# backplane_v3.net
KiCad netlist of a schematic drawn in EAGLE
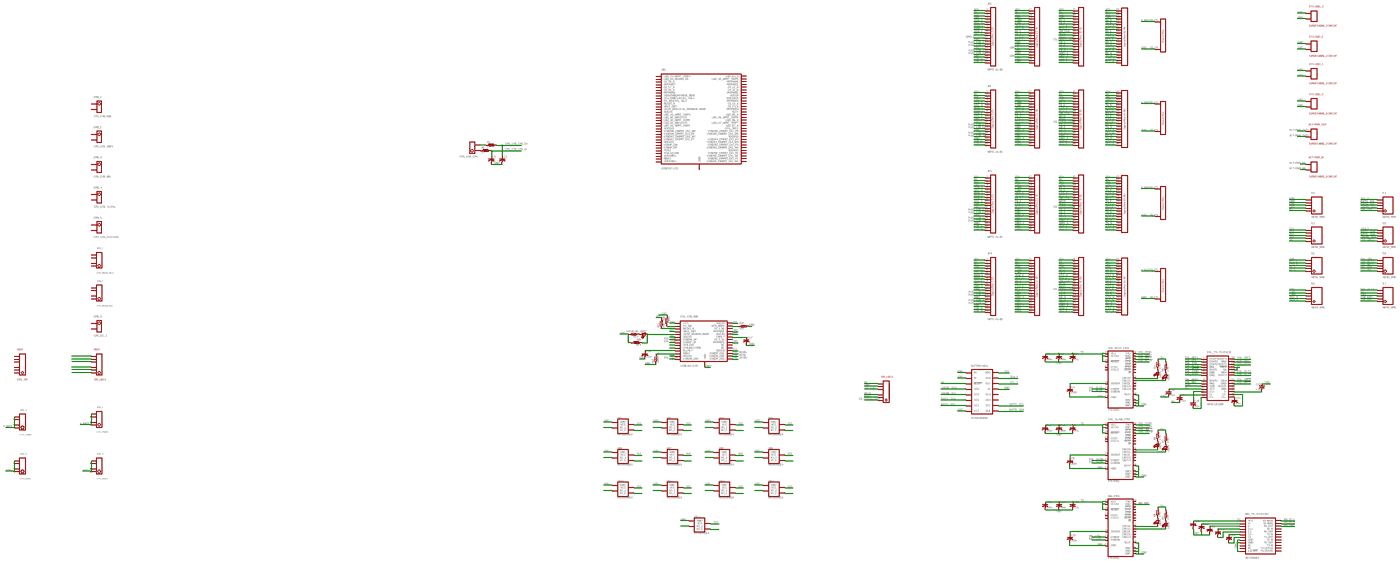
[diagram p0: schematic, sheet 1, overview]
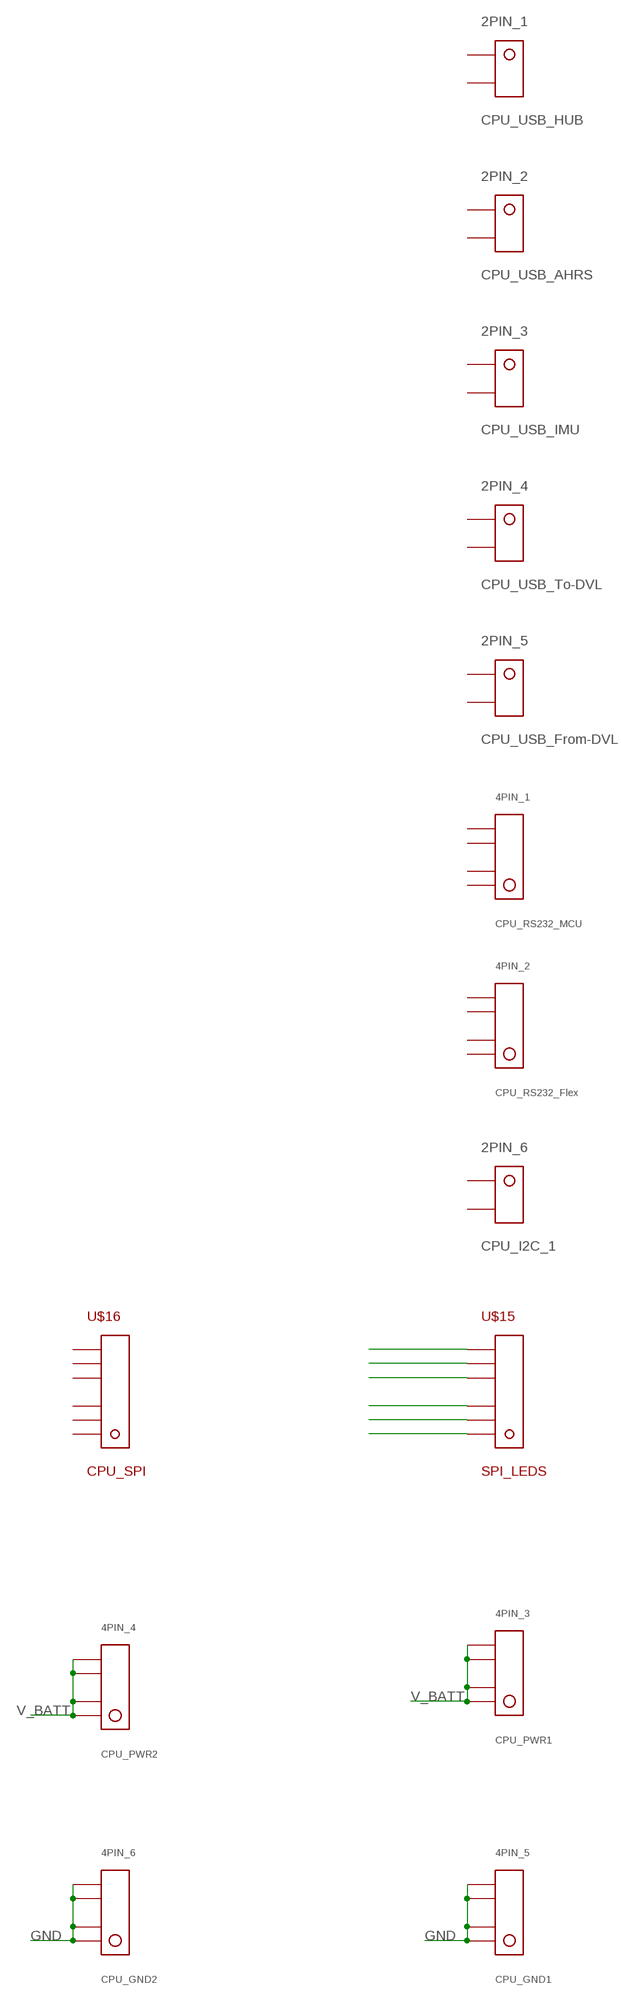
[diagram p1: schematic, sheet 1, part 1 of 4]
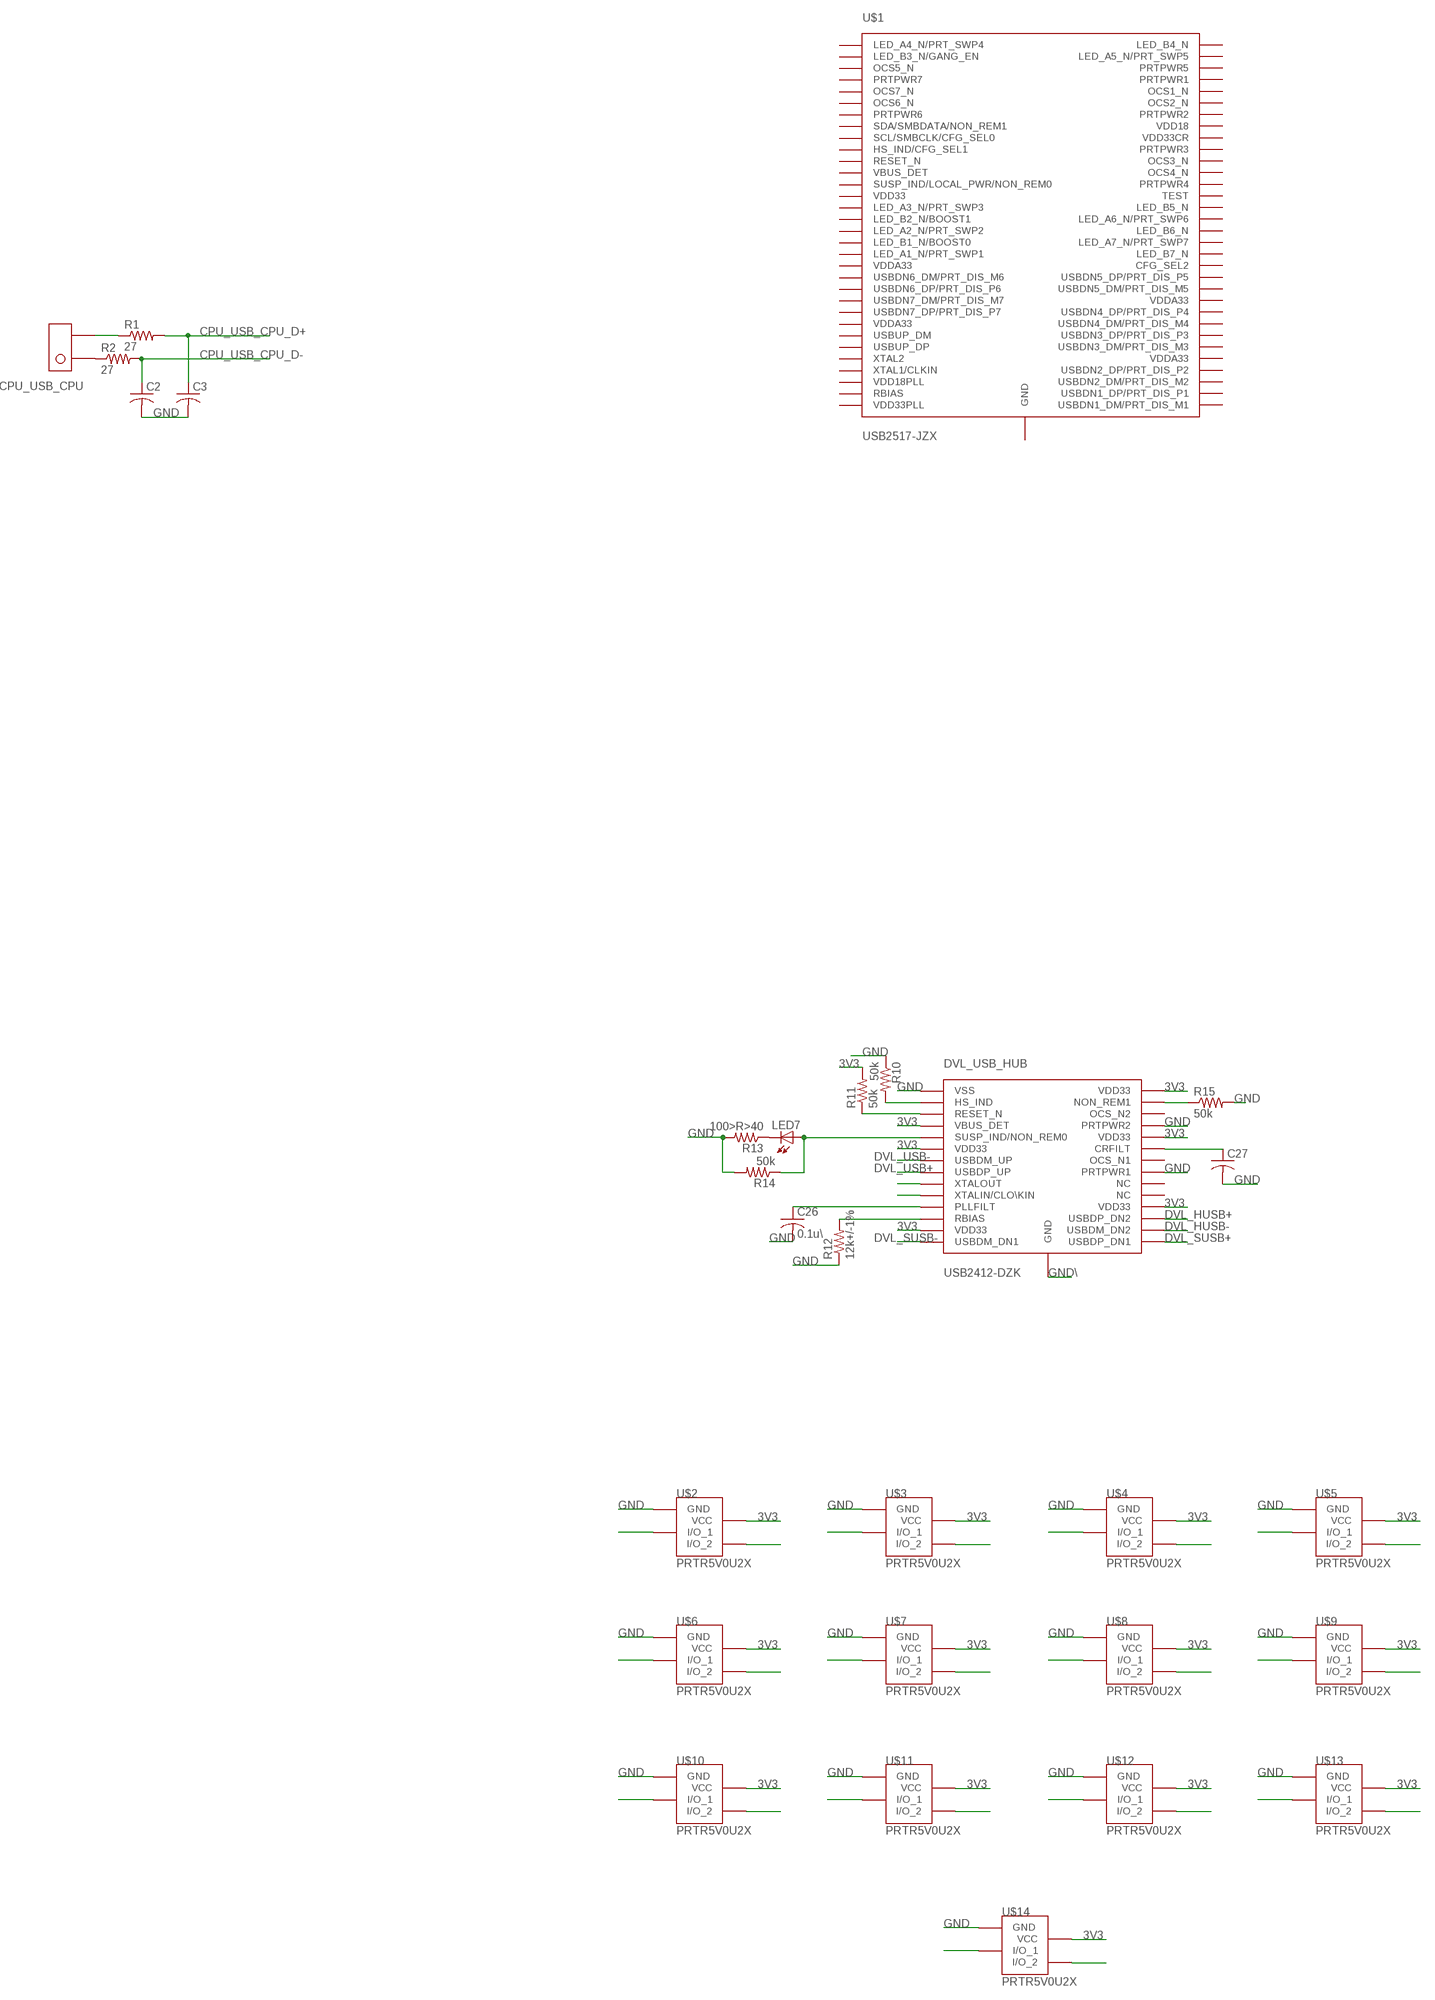
[diagram p2: schematic, sheet 1, part 2 of 4]
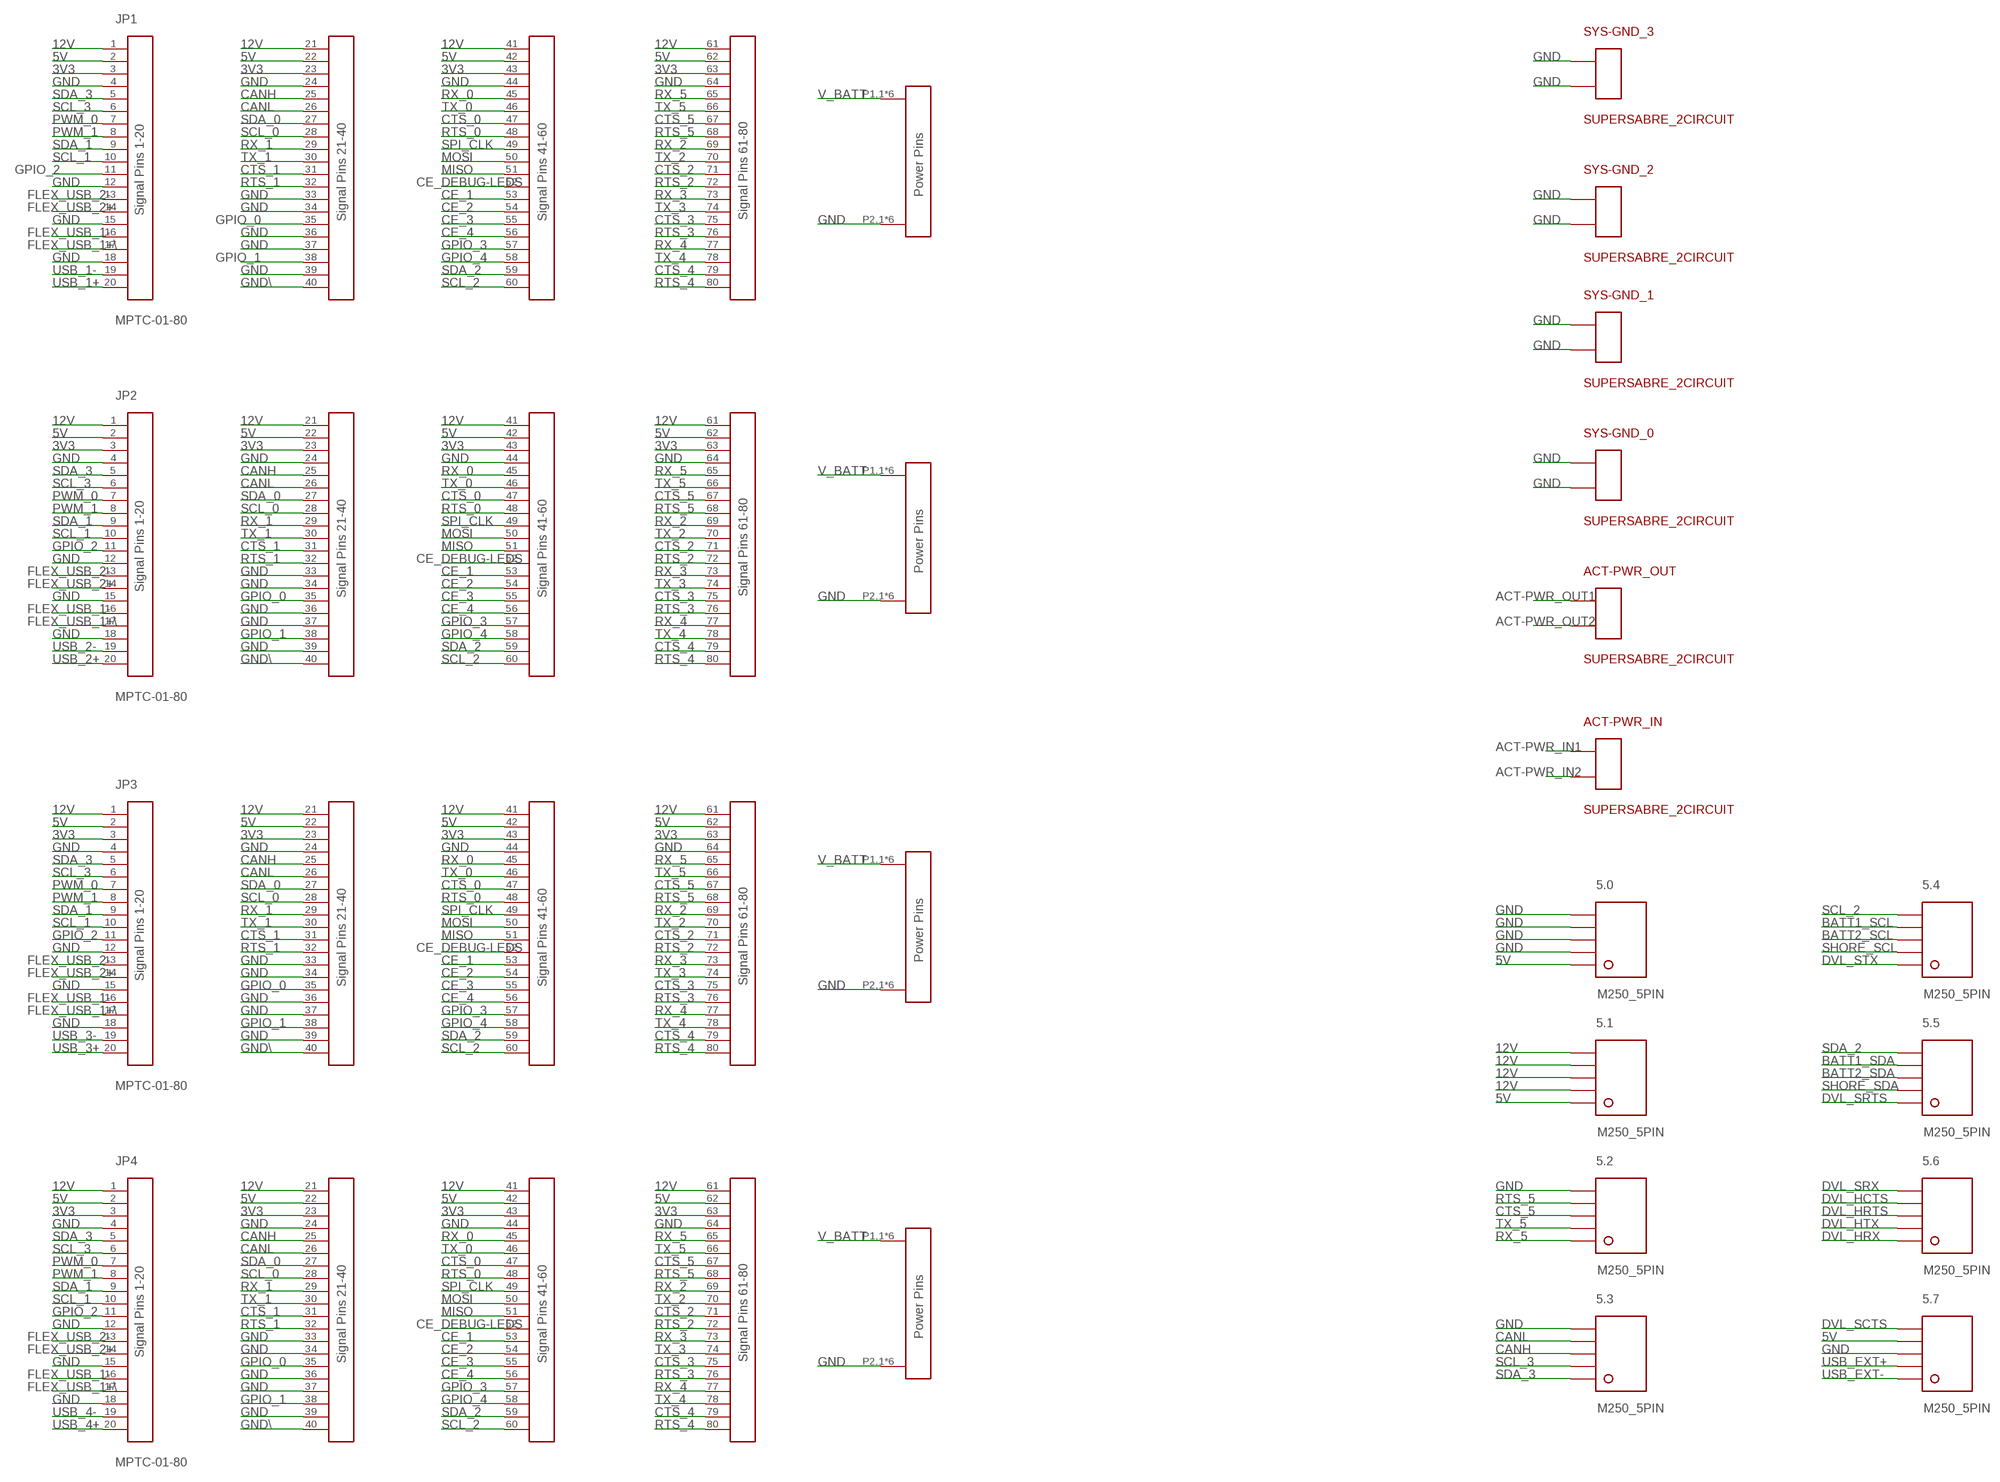
[diagram p3: schematic, sheet 1, part 3 of 4]
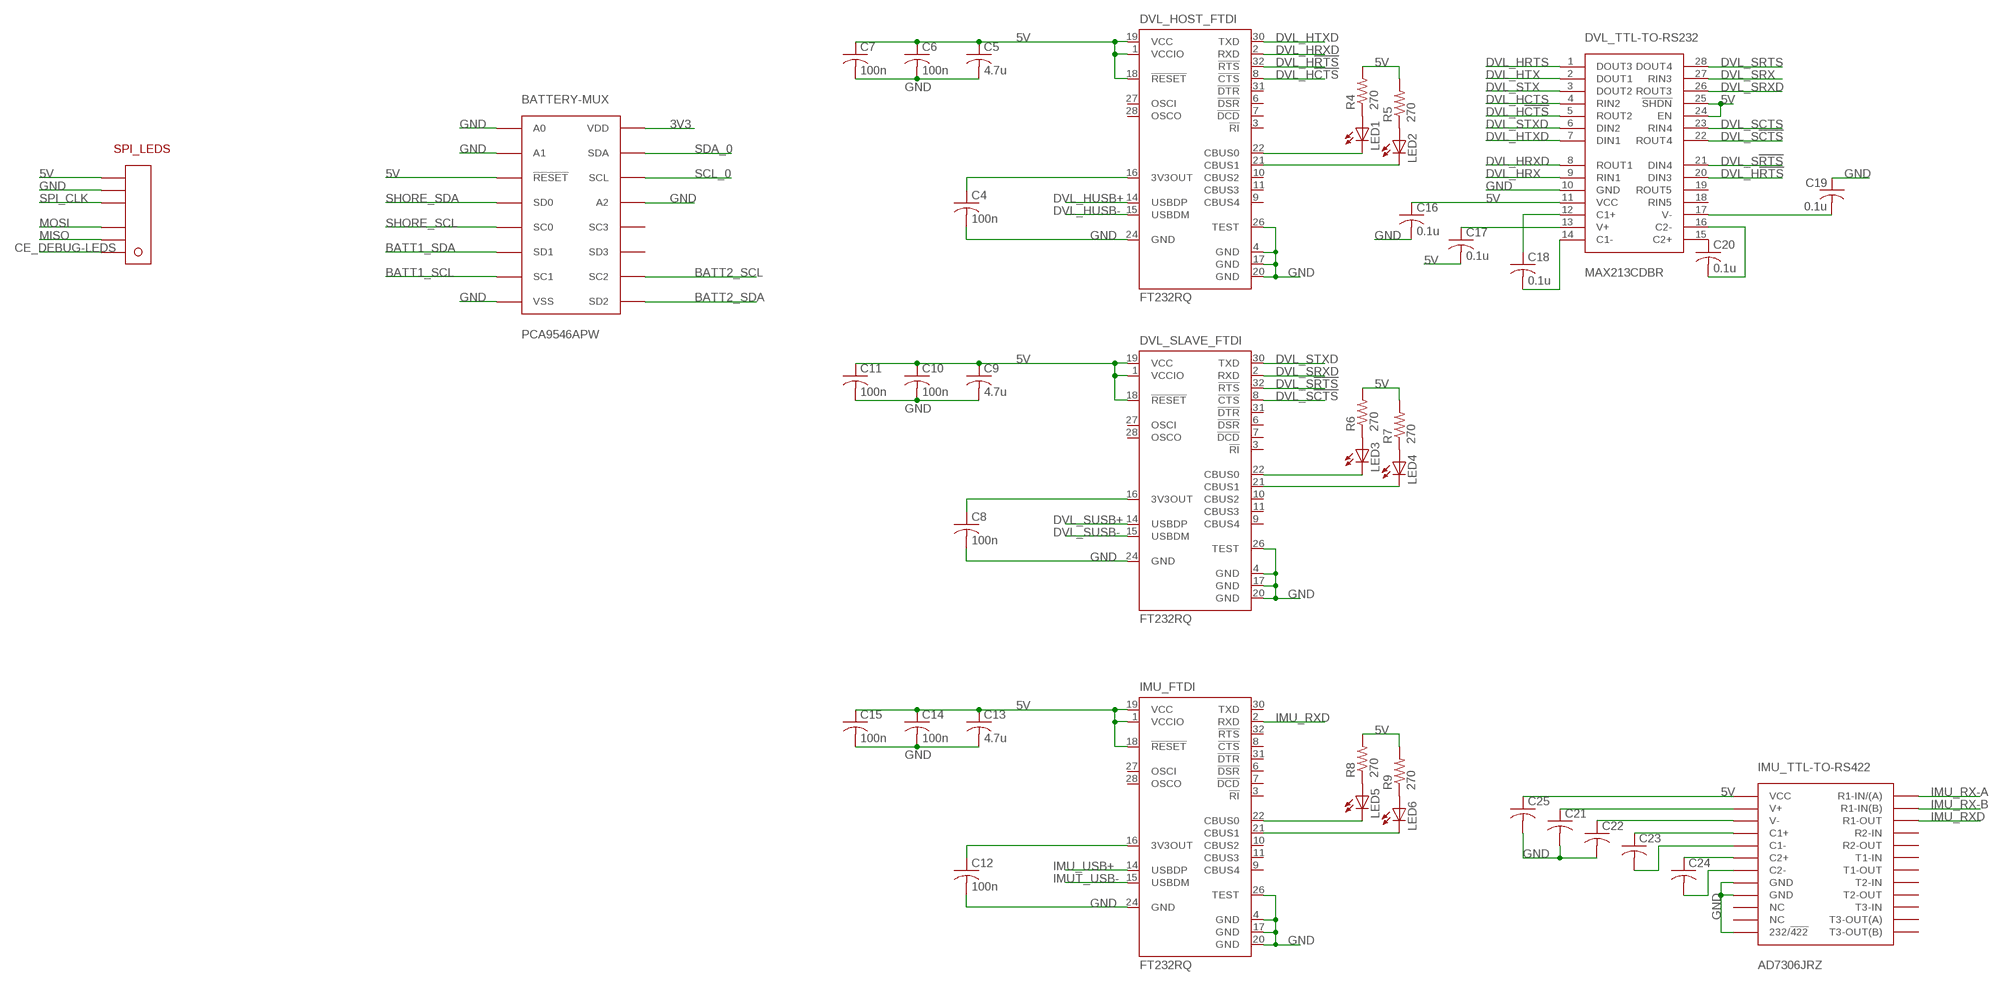
[diagram p4: schematic, sheet 1, part 4 of 4]

(export (version "E")
  (design (tool "Eeschema 10.0.6"))
  (components
    (comp (ref "2PIN_1")
      (value "CPU_USB_HUB")
      (footprint "eagle-import:KK254_VERT_2PIN")
      (libsource (lib "eagle-import") (part "KK254_VERT_2PIN22-29-2021"))
    )
    (comp (ref "2PIN_2")
      (value "CPU_USB_AHRS")
      (footprint "eagle-import:KK254_VERT_2PIN")
      (libsource (lib "eagle-import") (part "KK254_VERT_2PIN22-29-2021"))
    )
    (comp (ref "2PIN_3")
      (value "CPU_USB_IMU")
      (footprint "eagle-import:KK254_VERT_2PIN")
      (libsource (lib "eagle-import") (part "KK254_VERT_2PIN22-29-2021"))
    )
    (comp (ref "2PIN_4")
      (value "CPU_USB_To-DVL")
      (footprint "eagle-import:KK254_VERT_2PIN")
      (libsource (lib "eagle-import") (part "KK254_VERT_2PIN22-29-2021"))
    )
    (comp (ref "2PIN_5")
      (value "CPU_USB_From-DVL")
      (footprint "eagle-import:KK254_VERT_2PIN")
      (libsource (lib "eagle-import") (part "KK254_VERT_2PIN22-29-2021"))
    )
    (comp (ref "2PIN_6")
      (value "CPU_I2C_1")
      (footprint "eagle-import:KK254_VERT_2PIN")
      (libsource (lib "eagle-import") (part "KK254_VERT_2PIN22-29-2021"))
    )
    (comp (ref "4PIN_1")
      (value "CPU_RS232_MCU")
      (footprint "eagle-import:KK254_VERT_4PIN")
      (libsource (lib "eagle-import") (part "KK254_VERT_4PIN22-29-2041"))
    )
    (comp (ref "4PIN_2")
      (value "CPU_RS232_Flex")
      (footprint "eagle-import:KK254_VERT_4PIN")
      (libsource (lib "eagle-import") (part "KK254_VERT_4PIN22-29-2041"))
    )
    (comp (ref "4PIN_3")
      (value "CPU_PWR1")
      (footprint "eagle-import:KK254_VERT_4PIN")
      (libsource (lib "eagle-import") (part "KK254_VERT_4PIN22-29-2041"))
    )
    (comp (ref "4PIN_4")
      (value "CPU_PWR2")
      (footprint "eagle-import:KK254_VERT_4PIN")
      (libsource (lib "eagle-import") (part "KK254_VERT_4PIN22-29-2041"))
    )
    (comp (ref "4PIN_5")
      (value "CPU_GND1")
      (footprint "eagle-import:KK254_VERT_4PIN")
      (libsource (lib "eagle-import") (part "KK254_VERT_4PIN22-29-2041"))
    )
    (comp (ref "4PIN_6")
      (value "CPU_GND2")
      (footprint "eagle-import:KK254_VERT_4PIN")
      (libsource (lib "eagle-import") (part "KK254_VERT_4PIN22-29-2041"))
    )
    (comp (ref "5.0")
      (value "M250_5PIN")
      (footprint "eagle-import:M205_5PIN")
      (libsource (lib "eagle-import") (part "M250_5PIN"))
    )
    (comp (ref "5.1")
      (value "M250_5PIN")
      (footprint "eagle-import:M205_5PIN")
      (libsource (lib "eagle-import") (part "M250_5PIN"))
    )
    (comp (ref "5.2")
      (value "M250_5PIN")
      (footprint "eagle-import:M205_5PIN")
      (libsource (lib "eagle-import") (part "M250_5PIN"))
    )
    (comp (ref "5.3")
      (value "M250_5PIN")
      (footprint "eagle-import:M205_5PIN")
      (libsource (lib "eagle-import") (part "M250_5PIN"))
    )
    (comp (ref "5.4")
      (value "M250_5PIN")
      (footprint "eagle-import:M205_5PIN")
      (libsource (lib "eagle-import") (part "M250_5PIN"))
    )
    (comp (ref "5.5")
      (value "M250_5PIN")
      (footprint "eagle-import:M205_5PIN")
      (libsource (lib "eagle-import") (part "M250_5PIN"))
    )
    (comp (ref "5.6")
      (value "M250_5PIN")
      (footprint "eagle-import:M205_5PIN")
      (libsource (lib "eagle-import") (part "M250_5PIN"))
    )
    (comp (ref "5.7")
      (value "M250_5PIN")
      (footprint "eagle-import:M205_5PIN")
      (libsource (lib "eagle-import") (part "M250_5PIN"))
    )
    (comp (ref "ACT-PWR_IN")
      (value "SUPERSABRE_2CIRCUIT")
      (footprint "eagle-import:SUPERSABRE_2CIRCUIT")
      (libsource (lib "eagle-import") (part "SUPERSABRE_2CIRCUIT"))
    )
    (comp (ref "ACT-PWR_OUT")
      (value "SUPERSABRE_2CIRCUIT")
      (footprint "eagle-import:SUPERSABRE_2CIRCUIT")
      (libsource (lib "eagle-import") (part "SUPERSABRE_2CIRCUIT"))
    )
    (comp (ref "BATTERY-MUX")
      (value "PCA9546APW")
      (footprint "eagle-import:TSSOP16")
      (libsource (lib "eagle-import") (part "PCA9546APW"))
    )
    (comp (ref "C2")
      (value "C-USC0805")
      (footprint "eagle-import:C0805")
      (libsource (lib "eagle-import") (part "C-USC0805"))
    )
    (comp (ref "C3")
      (value "C-USC0805")
      (footprint "eagle-import:C0805")
      (libsource (lib "eagle-import") (part "C-USC0805"))
    )
    (comp (ref "C4")
      (value "100n")
      (footprint "eagle-import:C0805")
      (libsource (lib "eagle-import") (part "C-USC0805"))
    )
    (comp (ref "C5")
      (value "4.7u")
      (footprint "eagle-import:C0805")
      (libsource (lib "eagle-import") (part "C-USC0805"))
    )
    (comp (ref "C6")
      (value "100n")
      (footprint "eagle-import:C0805")
      (libsource (lib "eagle-import") (part "C-USC0805"))
    )
    (comp (ref "C7")
      (value "100n")
      (footprint "eagle-import:C0805")
      (libsource (lib "eagle-import") (part "C-USC0805"))
    )
    (comp (ref "C8")
      (value "100n")
      (footprint "eagle-import:C0805")
      (libsource (lib "eagle-import") (part "C-USC0805"))
    )
    (comp (ref "C9")
      (value "4.7u")
      (footprint "eagle-import:C0805")
      (libsource (lib "eagle-import") (part "C-USC0805"))
    )
    (comp (ref "C10")
      (value "100n")
      (footprint "eagle-import:C0805")
      (libsource (lib "eagle-import") (part "C-USC0805"))
    )
    (comp (ref "C11")
      (value "100n")
      (footprint "eagle-import:C0805")
      (libsource (lib "eagle-import") (part "C-USC0805"))
    )
    (comp (ref "C12")
      (value "100n")
      (footprint "eagle-import:C0805")
      (libsource (lib "eagle-import") (part "C-USC0805"))
    )
    (comp (ref "C13")
      (value "4.7u")
      (footprint "eagle-import:C0805")
      (libsource (lib "eagle-import") (part "C-USC0805"))
    )
    (comp (ref "C14")
      (value "100n")
      (footprint "eagle-import:C0805")
      (libsource (lib "eagle-import") (part "C-USC0805"))
    )
    (comp (ref "C15")
      (value "100n")
      (footprint "eagle-import:C0805")
      (libsource (lib "eagle-import") (part "C-USC0805"))
    )
    (comp (ref "C16")
      (value "0.1u")
      (footprint "eagle-import:C0805")
      (libsource (lib "eagle-import") (part "C-USC0805"))
    )
    (comp (ref "C17")
      (value "0.1u")
      (footprint "eagle-import:C0805")
      (libsource (lib "eagle-import") (part "C-USC0805"))
    )
    (comp (ref "C18")
      (value "0.1u")
      (footprint "eagle-import:C0805")
      (libsource (lib "eagle-import") (part "C-USC0805"))
    )
    (comp (ref "C19")
      (value "0.1u")
      (footprint "eagle-import:C0805")
      (libsource (lib "eagle-import") (part "C-USC0805"))
    )
    (comp (ref "C20")
      (value "0.1u")
      (footprint "eagle-import:C0805")
      (libsource (lib "eagle-import") (part "C-USC0805"))
    )
    (comp (ref "C21")
      (value "C-USC0805")
      (footprint "eagle-import:C0805")
      (libsource (lib "eagle-import") (part "C-USC0805"))
    )
    (comp (ref "C22")
      (value "C-USC0805")
      (footprint "eagle-import:C0805")
      (libsource (lib "eagle-import") (part "C-USC0805"))
    )
    (comp (ref "C23")
      (value "C-USC0805")
      (footprint "eagle-import:C0805")
      (libsource (lib "eagle-import") (part "C-USC0805"))
    )
    (comp (ref "C24")
      (value "C-USC0805")
      (footprint "eagle-import:C0805")
      (libsource (lib "eagle-import") (part "C-USC0805"))
    )
    (comp (ref "C25")
      (value "C-USC0805")
      (footprint "eagle-import:C0805")
      (libsource (lib "eagle-import") (part "C-USC0805"))
    )
    (comp (ref "C26")
      (value "0.1u\\")
      (footprint "eagle-import:C0805")
      (libsource (lib "eagle-import") (part "C-USC0805"))
    )
    (comp (ref "C27")
      (value "C-USC0805")
      (footprint "eagle-import:C0805")
      (libsource (lib "eagle-import") (part "C-USC0805"))
    )
    (comp (ref "CPU_USB_CPU")
      (value "KK254_VERT_2PIN22-29-2021")
      (footprint "eagle-import:KK254_VERT_2PIN")
      (libsource (lib "eagle-import") (part "KK254_VERT_2PIN22-29-2021"))
    )
    (comp (ref "DVL_HOST_FTDI")
      (value "FT232RQ")
      (footprint "eagle-import:QFN32")
      (libsource (lib "eagle-import") (part "FT232RQ"))
    )
    (comp (ref "DVL_SLAVE_FTDI")
      (value "FT232RQ")
      (footprint "eagle-import:QFN32")
      (libsource (lib "eagle-import") (part "FT232RQ"))
    )
    (comp (ref "DVL_TTL-TO-RS232")
      (value "MAX213CDBR")
      (footprint "eagle-import:SSOP28DB")
      (libsource (lib "eagle-import") (part "MAX213CDBR"))
    )
    (comp (ref "DVL_USB_HUB")
      (value "USB2412-DZK")
      (footprint "eagle-import:QFN-28")
      (libsource (lib "eagle-import") (part "USB2412-DZK"))
    )
    (comp (ref "IMU_FTDI")
      (value "FT232RQ")
      (footprint "eagle-import:QFN32")
      (libsource (lib "eagle-import") (part "FT232RQ"))
    )
    (comp (ref "IMU_TTL-TO-RS422")
      (value "AD7306JRZ")
      (footprint "eagle-import:SOIC-24")
      (libsource (lib "eagle-import") (part "AD7306JRZ"))
    )
    (comp (ref "JP1")
      (value "MPTC-01-80")
      (footprint "eagle-import:MPTC-01-80")
      (libsource (lib "eagle-import") (part "MPTC-01-80"))
    )
    (comp (ref "JP2")
      (value "MPTC-01-80")
      (footprint "eagle-import:MPTC-01-80")
      (libsource (lib "eagle-import") (part "MPTC-01-80"))
    )
    (comp (ref "JP3")
      (value "MPTC-01-80")
      (footprint "eagle-import:MPTC-01-80")
      (libsource (lib "eagle-import") (part "MPTC-01-80"))
    )
    (comp (ref "JP4")
      (value "MPTC-01-80")
      (footprint "eagle-import:MPTC-01-80")
      (libsource (lib "eagle-import") (part "MPTC-01-80"))
    )
    (comp (ref "LED1")
      (value "LEDCHIPLED_0805")
      (footprint "eagle-import:CHIPLED_0805")
      (libsource (lib "eagle-import") (part "LEDCHIPLED_0805"))
    )
    (comp (ref "LED2")
      (value "LEDCHIPLED_0805")
      (footprint "eagle-import:CHIPLED_0805")
      (libsource (lib "eagle-import") (part "LEDCHIPLED_0805"))
    )
    (comp (ref "LED3")
      (value "LEDCHIPLED_0805")
      (footprint "eagle-import:CHIPLED_0805")
      (libsource (lib "eagle-import") (part "LEDCHIPLED_0805"))
    )
    (comp (ref "LED4")
      (value "LEDCHIPLED_0805")
      (footprint "eagle-import:CHIPLED_0805")
      (libsource (lib "eagle-import") (part "LEDCHIPLED_0805"))
    )
    (comp (ref "LED5")
      (value "LEDCHIPLED_0805")
      (footprint "eagle-import:CHIPLED_0805")
      (libsource (lib "eagle-import") (part "LEDCHIPLED_0805"))
    )
    (comp (ref "LED6")
      (value "LEDCHIPLED_0805")
      (footprint "eagle-import:CHIPLED_0805")
      (libsource (lib "eagle-import") (part "LEDCHIPLED_0805"))
    )
    (comp (ref "LED7")
      (value "LEDCHIPLED_0805")
      (footprint "eagle-import:CHIPLED_0805")
      (libsource (lib "eagle-import") (part "LEDCHIPLED_0805"))
    )
    (comp (ref "R1")
      (value "27")
      (footprint "eagle-import:R0805")
      (libsource (lib "eagle-import") (part "R-US_R0805"))
    )
    (comp (ref "R2")
      (value "27")
      (footprint "eagle-import:R0805")
      (libsource (lib "eagle-import") (part "R-US_R0805"))
    )
    (comp (ref "R4")
      (value "270")
      (footprint "eagle-import:R0805")
      (libsource (lib "eagle-import") (part "R-US_R0805"))
    )
    (comp (ref "R5")
      (value "270")
      (footprint "eagle-import:R0805")
      (libsource (lib "eagle-import") (part "R-US_R0805"))
    )
    (comp (ref "R6")
      (value "270")
      (footprint "eagle-import:R0805")
      (libsource (lib "eagle-import") (part "R-US_R0805"))
    )
    (comp (ref "R7")
      (value "270")
      (footprint "eagle-import:R0805")
      (libsource (lib "eagle-import") (part "R-US_R0805"))
    )
    (comp (ref "R8")
      (value "270")
      (footprint "eagle-import:R0805")
      (libsource (lib "eagle-import") (part "R-US_R0805"))
    )
    (comp (ref "R9")
      (value "270")
      (footprint "eagle-import:R0805")
      (libsource (lib "eagle-import") (part "R-US_R0805"))
    )
    (comp (ref "R10")
      (value "50k")
      (footprint "eagle-import:R0805")
      (libsource (lib "eagle-import") (part "R-US_R0805"))
    )
    (comp (ref "R11")
      (value "50k")
      (footprint "eagle-import:R0805")
      (libsource (lib "eagle-import") (part "R-US_R0805"))
    )
    (comp (ref "R12")
      (value "12k+/-1%")
      (footprint "eagle-import:R0805")
      (libsource (lib "eagle-import") (part "R-US_R0805"))
    )
    (comp (ref "R13")
      (value "100>R>40")
      (footprint "eagle-import:R0805")
      (libsource (lib "eagle-import") (part "R-US_R0805"))
    )
    (comp (ref "R14")
      (value "50k")
      (footprint "eagle-import:R0805")
      (libsource (lib "eagle-import") (part "R-US_R0805"))
    )
    (comp (ref "R15")
      (value "50k")
      (footprint "eagle-import:R0805")
      (libsource (lib "eagle-import") (part "R-US_R0805"))
    )
    (comp (ref "SPI_LEDS")
      (value "KK254_6PIN")
      (footprint "eagle-import:KK254_6PIN")
      (libsource (lib "eagle-import") (part "KK254_6PIN"))
    )
    (comp (ref "SYS-GND_0")
      (value "SUPERSABRE_2CIRCUIT")
      (footprint "eagle-import:SUPERSABRE_2CIRCUIT")
      (libsource (lib "eagle-import") (part "SUPERSABRE_2CIRCUIT"))
    )
    (comp (ref "SYS-GND_1")
      (value "SUPERSABRE_2CIRCUIT")
      (footprint "eagle-import:SUPERSABRE_2CIRCUIT")
      (libsource (lib "eagle-import") (part "SUPERSABRE_2CIRCUIT"))
    )
    (comp (ref "SYS-GND_2")
      (value "SUPERSABRE_2CIRCUIT")
      (footprint "eagle-import:SUPERSABRE_2CIRCUIT")
      (libsource (lib "eagle-import") (part "SUPERSABRE_2CIRCUIT"))
    )
    (comp (ref "SYS-GND_3")
      (value "SUPERSABRE_2CIRCUIT")
      (footprint "eagle-import:SUPERSABRE_2CIRCUIT")
      (libsource (lib "eagle-import") (part "SUPERSABRE_2CIRCUIT"))
    )
    (comp (ref "U$1")
      (value "USB2517-JZX")
      (footprint "eagle-import:QFN-64")
      (libsource (lib "eagle-import") (part "USB2517-JZX"))
    )
    (comp (ref "U$2")
      (value "PRTR5V0U2X")
      (footprint "eagle-import:SOT143B")
      (libsource (lib "eagle-import") (part "PRTR5V0U2X"))
    )
    (comp (ref "U$3")
      (value "PRTR5V0U2X")
      (footprint "eagle-import:SOT143B")
      (libsource (lib "eagle-import") (part "PRTR5V0U2X"))
    )
    (comp (ref "U$4")
      (value "PRTR5V0U2X")
      (footprint "eagle-import:SOT143B")
      (libsource (lib "eagle-import") (part "PRTR5V0U2X"))
    )
    (comp (ref "U$5")
      (value "PRTR5V0U2X")
      (footprint "eagle-import:SOT143B")
      (libsource (lib "eagle-import") (part "PRTR5V0U2X"))
    )
    (comp (ref "U$6")
      (value "PRTR5V0U2X")
      (footprint "eagle-import:SOT143B")
      (libsource (lib "eagle-import") (part "PRTR5V0U2X"))
    )
    (comp (ref "U$7")
      (value "PRTR5V0U2X")
      (footprint "eagle-import:SOT143B")
      (libsource (lib "eagle-import") (part "PRTR5V0U2X"))
    )
    (comp (ref "U$8")
      (value "PRTR5V0U2X")
      (footprint "eagle-import:SOT143B")
      (libsource (lib "eagle-import") (part "PRTR5V0U2X"))
    )
    (comp (ref "U$9")
      (value "PRTR5V0U2X")
      (footprint "eagle-import:SOT143B")
      (libsource (lib "eagle-import") (part "PRTR5V0U2X"))
    )
    (comp (ref "U$10")
      (value "PRTR5V0U2X")
      (footprint "eagle-import:SOT143B")
      (libsource (lib "eagle-import") (part "PRTR5V0U2X"))
    )
    (comp (ref "U$11")
      (value "PRTR5V0U2X")
      (footprint "eagle-import:SOT143B")
      (libsource (lib "eagle-import") (part "PRTR5V0U2X"))
    )
    (comp (ref "U$12")
      (value "PRTR5V0U2X")
      (footprint "eagle-import:SOT143B")
      (libsource (lib "eagle-import") (part "PRTR5V0U2X"))
    )
    (comp (ref "U$13")
      (value "PRTR5V0U2X")
      (footprint "eagle-import:SOT143B")
      (libsource (lib "eagle-import") (part "PRTR5V0U2X"))
    )
    (comp (ref "U$14")
      (value "PRTR5V0U2X")
      (footprint "eagle-import:SOT143B")
      (libsource (lib "eagle-import") (part "PRTR5V0U2X"))
    )
    (comp (ref "U$15")
      (value "SPI_LEDS")
      (footprint "eagle-import:KK254_6PIN")
      (libsource (lib "eagle-import") (part "KK254_6PIN"))
    )
    (comp (ref "U$16")
      (value "CPU_SPI")
      (footprint "eagle-import:KK254_6PIN")
      (libsource (lib "eagle-import") (part "KK254_6PIN"))
    )
  )
  (nets
    (net (code "1") (name "/3V3") (class "Default")
      (node (ref "BATTERY-MUX") (pin "P$16") (pinfunction "VDD_P$16") (pintype "bidirectional"))
      (node (ref "DVL_USB_HUB") (pin "P$10") (pinfunction "VDD33_P$10") (pintype "bidirectional"))
      (node (ref "DVL_USB_HUB") (pin "P$14") (pinfunction "VDD33_P$14") (pintype "bidirectional"))
      (node (ref "DVL_USB_HUB") (pin "P$18") (pinfunction "VBUS_DET_P$18") (pintype "bidirectional"))
      (node (ref "DVL_USB_HUB") (pin "P$20") (pinfunction "VDD33_P$20") (pintype "bidirectional"))
      (node (ref "DVL_USB_HUB") (pin "P$27") (pinfunction "VDD33_P$27") (pintype "bidirectional"))
      (node (ref "DVL_USB_HUB") (pin "P$4") (pinfunction "VDD33_P$4") (pintype "bidirectional"))
      (node (ref "JP1") (pin "23") (pinfunction "P$23_23") (pintype "bidirectional"))
      (node (ref "JP1") (pin "3") (pinfunction "P$3_3") (pintype "bidirectional"))
      (node (ref "JP1") (pin "43") (pinfunction "P$43_43") (pintype "bidirectional"))
      (node (ref "JP1") (pin "63") (pinfunction "P$63_63") (pintype "bidirectional"))
      (node (ref "JP2") (pin "23") (pinfunction "P$23_23") (pintype "bidirectional"))
      (node (ref "JP2") (pin "3") (pinfunction "P$3_3") (pintype "bidirectional"))
      (node (ref "JP2") (pin "43") (pinfunction "P$43_43") (pintype "bidirectional"))
      (node (ref "JP2") (pin "63") (pinfunction "P$63_63") (pintype "bidirectional"))
      (node (ref "JP3") (pin "23") (pinfunction "P$23_23") (pintype "bidirectional"))
      (node (ref "JP3") (pin "3") (pinfunction "P$3_3") (pintype "bidirectional"))
      (node (ref "JP3") (pin "43") (pinfunction "P$43_43") (pintype "bidirectional"))
      (node (ref "JP3") (pin "63") (pinfunction "P$63_63") (pintype "bidirectional"))
      (node (ref "JP4") (pin "23") (pinfunction "P$23_23") (pintype "bidirectional"))
      (node (ref "JP4") (pin "3") (pinfunction "P$3_3") (pintype "bidirectional"))
      (node (ref "JP4") (pin "43") (pinfunction "P$43_43") (pintype "bidirectional"))
      (node (ref "JP4") (pin "63") (pinfunction "P$63_63") (pintype "bidirectional"))
      (node (ref "R11") (pin "2") (pinfunction "2_2") (pintype "passive"))
      (node (ref "U$10") (pin "P$4") (pinfunction "VCC_P$4") (pintype "bidirectional"))
      (node (ref "U$11") (pin "P$4") (pinfunction "VCC_P$4") (pintype "bidirectional"))
      (node (ref "U$12") (pin "P$4") (pinfunction "VCC_P$4") (pintype "bidirectional"))
      (node (ref "U$13") (pin "P$4") (pinfunction "VCC_P$4") (pintype "bidirectional"))
      (node (ref "U$14") (pin "P$4") (pinfunction "VCC_P$4") (pintype "bidirectional"))
      (node (ref "U$2") (pin "P$4") (pinfunction "VCC_P$4") (pintype "bidirectional"))
      (node (ref "U$3") (pin "P$4") (pinfunction "VCC_P$4") (pintype "bidirectional"))
      (node (ref "U$4") (pin "P$4") (pinfunction "VCC_P$4") (pintype "bidirectional"))
      (node (ref "U$5") (pin "P$4") (pinfunction "VCC_P$4") (pintype "bidirectional"))
      (node (ref "U$6") (pin "P$4") (pinfunction "VCC_P$4") (pintype "bidirectional"))
      (node (ref "U$7") (pin "P$4") (pinfunction "VCC_P$4") (pintype "bidirectional"))
      (node (ref "U$8") (pin "P$4") (pinfunction "VCC_P$4") (pintype "bidirectional"))
      (node (ref "U$9") (pin "P$4") (pinfunction "VCC_P$4") (pintype "bidirectional"))
    )
    (net (code "2") (name "/5V") (class "Default")
      (node (ref "5.0") (pin "P$1") (pinfunction "P$1_P$1") (pintype "bidirectional"))
      (node (ref "5.0") (pin "P$2") (pinfunction "P$1_P$2") (pintype "bidirectional"))
      (node (ref "5.1") (pin "P$1") (pinfunction "P$1_P$1") (pintype "bidirectional"))
      (node (ref "5.1") (pin "P$2") (pinfunction "P$1_P$2") (pintype "bidirectional"))
      (node (ref "5.7") (pin "P$7") (pinfunction "P$4_P$7") (pintype "bidirectional"))
      (node (ref "5.7") (pin "P$8") (pinfunction "P$4_P$8") (pintype "bidirectional"))
      (node (ref "BATTERY-MUX") (pin "P$3") (pinfunction "~{RESET}_P$3") (pintype "bidirectional"))
      (node (ref "C10") (pin "1") (pinfunction "1_1") (pintype "passive"))
      (node (ref "C11") (pin "1") (pinfunction "1_1") (pintype "passive"))
      (node (ref "C13") (pin "1") (pinfunction "1_1") (pintype "passive"))
      (node (ref "C14") (pin "1") (pinfunction "1_1") (pintype "passive"))
      (node (ref "C15") (pin "1") (pinfunction "1_1") (pintype "passive"))
      (node (ref "C16") (pin "1") (pinfunction "1_1") (pintype "passive"))
      (node (ref "C17") (pin "2") (pinfunction "2_2") (pintype "passive"))
      (node (ref "C25") (pin "1") (pinfunction "1_1") (pintype "passive"))
      (node (ref "C5") (pin "1") (pinfunction "1_1") (pintype "passive"))
      (node (ref "C6") (pin "1") (pinfunction "1_1") (pintype "passive"))
      (node (ref "C7") (pin "1") (pinfunction "1_1") (pintype "passive"))
      (node (ref "C9") (pin "1") (pinfunction "1_1") (pintype "passive"))
      (node (ref "DVL_HOST_FTDI") (pin "1") (pinfunction "VCCIO_1") (pintype "power_in"))
      (node (ref "DVL_HOST_FTDI") (pin "18") (pinfunction "~{RESET}_18") (pintype "input"))
      (node (ref "DVL_HOST_FTDI") (pin "19") (pinfunction "VCC_19") (pintype "power_in"))
      (node (ref "DVL_SLAVE_FTDI") (pin "1") (pinfunction "VCCIO_1") (pintype "power_in"))
      (node (ref "DVL_SLAVE_FTDI") (pin "18") (pinfunction "~{RESET}_18") (pintype "input"))
      (node (ref "DVL_SLAVE_FTDI") (pin "19") (pinfunction "VCC_19") (pintype "power_in"))
      (node (ref "DVL_TTL-TO-RS232") (pin "11") (pinfunction "VCC_11") (pintype "bidirectional"))
      (node (ref "DVL_TTL-TO-RS232") (pin "24") (pinfunction "EN_24") (pintype "bidirectional"))
      (node (ref "DVL_TTL-TO-RS232") (pin "25") (pinfunction "~{SHDN}_25") (pintype "bidirectional"))
      (node (ref "IMU_FTDI") (pin "1") (pinfunction "VCCIO_1") (pintype "power_in"))
      (node (ref "IMU_FTDI") (pin "18") (pinfunction "~{RESET}_18") (pintype "input"))
      (node (ref "IMU_FTDI") (pin "19") (pinfunction "VCC_19") (pintype "power_in"))
      (node (ref "IMU_TTL-TO-RS422") (pin "P$7") (pinfunction "VCC_P$7") (pintype "bidirectional"))
      (node (ref "JP1") (pin "2") (pinfunction "P$2_2") (pintype "bidirectional"))
      (node (ref "JP1") (pin "22") (pinfunction "P$22_22") (pintype "bidirectional"))
      (node (ref "JP1") (pin "42") (pinfunction "P$42_42") (pintype "bidirectional"))
      (node (ref "JP1") (pin "62") (pinfunction "P$62_62") (pintype "bidirectional"))
      (node (ref "JP2") (pin "2") (pinfunction "P$2_2") (pintype "bidirectional"))
      (node (ref "JP2") (pin "22") (pinfunction "P$22_22") (pintype "bidirectional"))
      (node (ref "JP2") (pin "42") (pinfunction "P$42_42") (pintype "bidirectional"))
      (node (ref "JP2") (pin "62") (pinfunction "P$62_62") (pintype "bidirectional"))
      (node (ref "JP3") (pin "2") (pinfunction "P$2_2") (pintype "bidirectional"))
      (node (ref "JP3") (pin "22") (pinfunction "P$22_22") (pintype "bidirectional"))
      (node (ref "JP3") (pin "42") (pinfunction "P$42_42") (pintype "bidirectional"))
      (node (ref "JP3") (pin "62") (pinfunction "P$62_62") (pintype "bidirectional"))
      (node (ref "JP4") (pin "2") (pinfunction "P$2_2") (pintype "bidirectional"))
      (node (ref "JP4") (pin "22") (pinfunction "P$22_22") (pintype "bidirectional"))
      (node (ref "JP4") (pin "42") (pinfunction "P$42_42") (pintype "bidirectional"))
      (node (ref "JP4") (pin "62") (pinfunction "P$62_62") (pintype "bidirectional"))
      (node (ref "R4") (pin "2") (pinfunction "2_2") (pintype "passive"))
      (node (ref "R5") (pin "2") (pinfunction "2_2") (pintype "passive"))
      (node (ref "R6") (pin "2") (pinfunction "2_2") (pintype "passive"))
      (node (ref "R7") (pin "2") (pinfunction "2_2") (pintype "passive"))
      (node (ref "R8") (pin "2") (pinfunction "2_2") (pintype "passive"))
      (node (ref "R9") (pin "2") (pinfunction "2_2") (pintype "passive"))
      (node (ref "SPI_LEDS") (pin "P$6") (pinfunction "P$6_P$6") (pintype "bidirectional"))
    )
    (net (code "3") (name "/12V") (class "Default")
      (node (ref "5.1") (pin "P$10") (pinfunction "P$5_P$10") (pintype "bidirectional"))
      (node (ref "5.1") (pin "P$3") (pinfunction "P$2_P$3") (pintype "bidirectional"))
      (node (ref "5.1") (pin "P$4") (pinfunction "P$2_P$4") (pintype "bidirectional"))
      (node (ref "5.1") (pin "P$5") (pinfunction "P$3_P$5") (pintype "bidirectional"))
      (node (ref "5.1") (pin "P$6") (pinfunction "P$3_P$6") (pintype "bidirectional"))
      (node (ref "5.1") (pin "P$7") (pinfunction "P$4_P$7") (pintype "bidirectional"))
      (node (ref "5.1") (pin "P$8") (pinfunction "P$4_P$8") (pintype "bidirectional"))
      (node (ref "5.1") (pin "P$9") (pinfunction "P$5_P$9") (pintype "bidirectional"))
      (node (ref "JP1") (pin "1") (pinfunction "P$1_1") (pintype "bidirectional"))
      (node (ref "JP1") (pin "21") (pinfunction "P$21_21") (pintype "bidirectional"))
      (node (ref "JP1") (pin "41") (pinfunction "P$41_41") (pintype "bidirectional"))
      (node (ref "JP1") (pin "61") (pinfunction "P$61_61") (pintype "bidirectional"))
      (node (ref "JP2") (pin "1") (pinfunction "P$1_1") (pintype "bidirectional"))
      (node (ref "JP2") (pin "21") (pinfunction "P$21_21") (pintype "bidirectional"))
      (node (ref "JP2") (pin "41") (pinfunction "P$41_41") (pintype "bidirectional"))
      (node (ref "JP2") (pin "61") (pinfunction "P$61_61") (pintype "bidirectional"))
      (node (ref "JP3") (pin "1") (pinfunction "P$1_1") (pintype "bidirectional"))
      (node (ref "JP3") (pin "21") (pinfunction "P$21_21") (pintype "bidirectional"))
      (node (ref "JP3") (pin "41") (pinfunction "P$41_41") (pintype "bidirectional"))
      (node (ref "JP3") (pin "61") (pinfunction "P$61_61") (pintype "bidirectional"))
      (node (ref "JP4") (pin "1") (pinfunction "P$1_1") (pintype "bidirectional"))
      (node (ref "JP4") (pin "21") (pinfunction "P$21_21") (pintype "bidirectional"))
      (node (ref "JP4") (pin "41") (pinfunction "P$41_41") (pintype "bidirectional"))
      (node (ref "JP4") (pin "61") (pinfunction "P$61_61") (pintype "bidirectional"))
    )
    (net (code "4") (name "/ACT-PWR_IN1") (class "Default")
      (node (ref "ACT-PWR_IN") (pin "P$1") (pinfunction "P$1_P$1") (pintype "bidirectional"))
    )
    (net (code "5") (name "/ACT-PWR_IN2") (class "Default")
      (node (ref "ACT-PWR_IN") (pin "P$2") (pinfunction "P$2_P$2") (pintype "bidirectional"))
    )
    (net (code "6") (name "/ACT-PWR_OUT1") (class "Default")
      (node (ref "ACT-PWR_OUT") (pin "P$1") (pinfunction "P$1_P$1") (pintype "bidirectional"))
    )
    (net (code "7") (name "/ACT-PWR_OUT2") (class "Default")
      (node (ref "ACT-PWR_OUT") (pin "P$2") (pinfunction "P$2_P$2") (pintype "bidirectional"))
    )
    (net (code "8") (name "/BATT1_SCL") (class "Default")
      (node (ref "5.4") (pin "P$7") (pinfunction "P$4_P$7") (pintype "bidirectional"))
      (node (ref "5.4") (pin "P$8") (pinfunction "P$4_P$8") (pintype "bidirectional"))
      (node (ref "BATTERY-MUX") (pin "P$7") (pinfunction "SC1_P$7") (pintype "bidirectional"))
    )
    (net (code "9") (name "/BATT1_SDA") (class "Default")
      (node (ref "5.5") (pin "P$7") (pinfunction "P$4_P$7") (pintype "bidirectional"))
      (node (ref "5.5") (pin "P$8") (pinfunction "P$4_P$8") (pintype "bidirectional"))
      (node (ref "BATTERY-MUX") (pin "P$6") (pinfunction "SD1_P$6") (pintype "bidirectional"))
    )
    (net (code "10") (name "/BATT2_SCL") (class "Default")
      (node (ref "5.4") (pin "P$5") (pinfunction "P$3_P$5") (pintype "bidirectional"))
      (node (ref "5.4") (pin "P$6") (pinfunction "P$3_P$6") (pintype "bidirectional"))
      (node (ref "BATTERY-MUX") (pin "P$10") (pinfunction "SC2_P$10") (pintype "bidirectional"))
    )
    (net (code "11") (name "/BATT2_SDA") (class "Default")
      (node (ref "5.5") (pin "P$5") (pinfunction "P$3_P$5") (pintype "bidirectional"))
      (node (ref "5.5") (pin "P$6") (pinfunction "P$3_P$6") (pintype "bidirectional"))
      (node (ref "BATTERY-MUX") (pin "P$9") (pinfunction "SD2_P$9") (pintype "bidirectional"))
    )
    (net (code "12") (name "/CANH") (class "Default")
      (node (ref "5.3") (pin "P$5") (pinfunction "P$3_P$5") (pintype "bidirectional"))
      (node (ref "5.3") (pin "P$6") (pinfunction "P$3_P$6") (pintype "bidirectional"))
      (node (ref "JP1") (pin "25") (pinfunction "P$25_25") (pintype "bidirectional"))
      (node (ref "JP2") (pin "25") (pinfunction "P$25_25") (pintype "bidirectional"))
      (node (ref "JP3") (pin "25") (pinfunction "P$25_25") (pintype "bidirectional"))
      (node (ref "JP4") (pin "25") (pinfunction "P$25_25") (pintype "bidirectional"))
    )
    (net (code "13") (name "/CANL") (class "Default")
      (node (ref "5.3") (pin "P$7") (pinfunction "P$4_P$7") (pintype "bidirectional"))
      (node (ref "5.3") (pin "P$8") (pinfunction "P$4_P$8") (pintype "bidirectional"))
      (node (ref "JP1") (pin "26") (pinfunction "P$26_26") (pintype "bidirectional"))
      (node (ref "JP2") (pin "26") (pinfunction "P$26_26") (pintype "bidirectional"))
      (node (ref "JP3") (pin "26") (pinfunction "P$26_26") (pintype "bidirectional"))
      (node (ref "JP4") (pin "26") (pinfunction "P$26_26") (pintype "bidirectional"))
    )
    (net (code "14") (name "/CE_1") (class "Default")
      (node (ref "JP1") (pin "53") (pinfunction "P$53_53") (pintype "bidirectional"))
      (node (ref "JP2") (pin "53") (pinfunction "P$53_53") (pintype "bidirectional"))
      (node (ref "JP3") (pin "53") (pinfunction "P$53_53") (pintype "bidirectional"))
      (node (ref "JP4") (pin "53") (pinfunction "P$53_53") (pintype "bidirectional"))
    )
    (net (code "15") (name "/CE_2") (class "Default")
      (node (ref "JP1") (pin "54") (pinfunction "P$54_54") (pintype "bidirectional"))
      (node (ref "JP2") (pin "54") (pinfunction "P$54_54") (pintype "bidirectional"))
      (node (ref "JP3") (pin "54") (pinfunction "P$54_54") (pintype "bidirectional"))
      (node (ref "JP4") (pin "54") (pinfunction "P$54_54") (pintype "bidirectional"))
    )
    (net (code "16") (name "/CE_3") (class "Default")
      (node (ref "JP1") (pin "55") (pinfunction "P$55_55") (pintype "bidirectional"))
      (node (ref "JP2") (pin "55") (pinfunction "P$55_55") (pintype "bidirectional"))
      (node (ref "JP3") (pin "55") (pinfunction "P$55_55") (pintype "bidirectional"))
      (node (ref "JP4") (pin "55") (pinfunction "P$55_55") (pintype "bidirectional"))
    )
    (net (code "17") (name "/CE_4") (class "Default")
      (node (ref "JP1") (pin "56") (pinfunction "P$56_56") (pintype "bidirectional"))
      (node (ref "JP2") (pin "56") (pinfunction "P$56_56") (pintype "bidirectional"))
      (node (ref "JP3") (pin "56") (pinfunction "P$56_56") (pintype "bidirectional"))
      (node (ref "JP4") (pin "56") (pinfunction "P$56_56") (pintype "bidirectional"))
    )
    (net (code "18") (name "/CE_DEBUG-LEDS") (class "Default")
      (node (ref "JP1") (pin "52") (pinfunction "P$52_52") (pintype "bidirectional"))
      (node (ref "JP2") (pin "52") (pinfunction "P$52_52") (pintype "bidirectional"))
      (node (ref "JP3") (pin "52") (pinfunction "P$52_52") (pintype "bidirectional"))
      (node (ref "JP4") (pin "52") (pinfunction "P$52_52") (pintype "bidirectional"))
      (node (ref "SPI_LEDS") (pin "P$1") (pinfunction "P$1_P$1") (pintype "bidirectional"))
    )
    (net (code "19") (name "/CPU_USB_CPU_D+") (class "Default")
      (node (ref "C3") (pin "1") (pinfunction "1_1") (pintype "passive"))
      (node (ref "R1") (pin "2") (pinfunction "2_2") (pintype "passive"))
    )
    (net (code "20") (name "/CPU_USB_CPU_D-") (class "Default")
      (node (ref "C2") (pin "1") (pinfunction "1_1") (pintype "passive"))
      (node (ref "R2") (pin "2") (pinfunction "2_2") (pintype "passive"))
    )
    (net (code "21") (name "/CTS_0") (class "Default")
      (node (ref "JP1") (pin "47") (pinfunction "P$47_47") (pintype "bidirectional"))
      (node (ref "JP2") (pin "47") (pinfunction "P$47_47") (pintype "bidirectional"))
      (node (ref "JP3") (pin "47") (pinfunction "P$47_47") (pintype "bidirectional"))
      (node (ref "JP4") (pin "47") (pinfunction "P$47_47") (pintype "bidirectional"))
    )
    (net (code "22") (name "/CTS_1") (class "Default")
      (node (ref "JP1") (pin "31") (pinfunction "P$31_31") (pintype "bidirectional"))
      (node (ref "JP2") (pin "31") (pinfunction "P$31_31") (pintype "bidirectional"))
      (node (ref "JP3") (pin "31") (pinfunction "P$31_31") (pintype "bidirectional"))
      (node (ref "JP4") (pin "31") (pinfunction "P$31_31") (pintype "bidirectional"))
    )
    (net (code "23") (name "/CTS_2") (class "Default")
      (node (ref "JP1") (pin "71") (pinfunction "P$71_71") (pintype "bidirectional"))
      (node (ref "JP2") (pin "71") (pinfunction "P$71_71") (pintype "bidirectional"))
      (node (ref "JP3") (pin "71") (pinfunction "P$71_71") (pintype "bidirectional"))
      (node (ref "JP4") (pin "71") (pinfunction "P$71_71") (pintype "bidirectional"))
    )
    (net (code "24") (name "/CTS_3") (class "Default")
      (node (ref "JP1") (pin "75") (pinfunction "P$75_75") (pintype "bidirectional"))
      (node (ref "JP2") (pin "75") (pinfunction "P$75_75") (pintype "bidirectional"))
      (node (ref "JP3") (pin "75") (pinfunction "P$75_75") (pintype "bidirectional"))
      (node (ref "JP4") (pin "75") (pinfunction "P$75_75") (pintype "bidirectional"))
    )
    (net (code "25") (name "/CTS_4") (class "Default")
      (node (ref "JP1") (pin "79") (pinfunction "P$79_79") (pintype "bidirectional"))
      (node (ref "JP2") (pin "79") (pinfunction "P$79_79") (pintype "bidirectional"))
      (node (ref "JP3") (pin "79") (pinfunction "P$79_79") (pintype "bidirectional"))
      (node (ref "JP4") (pin "79") (pinfunction "P$79_79") (pintype "bidirectional"))
    )
    (net (code "26") (name "/CTS_5") (class "Default")
      (node (ref "5.2") (pin "P$5") (pinfunction "P$3_P$5") (pintype "bidirectional"))
      (node (ref "5.2") (pin "P$6") (pinfunction "P$3_P$6") (pintype "bidirectional"))
      (node (ref "JP1") (pin "67") (pinfunction "P$67_67") (pintype "bidirectional"))
      (node (ref "JP2") (pin "67") (pinfunction "P$67_67") (pintype "bidirectional"))
      (node (ref "JP3") (pin "67") (pinfunction "P$67_67") (pintype "bidirectional"))
      (node (ref "JP4") (pin "67") (pinfunction "P$67_67") (pintype "bidirectional"))
    )
    (net (code "27") (name "/DVL_HCTS") (class "Default")
      (node (ref "5.6") (pin "P$7") (pinfunction "P$4_P$7") (pintype "bidirectional"))
      (node (ref "5.6") (pin "P$8") (pinfunction "P$4_P$8") (pintype "bidirectional"))
      (node (ref "DVL_TTL-TO-RS232") (pin "4") (pinfunction "RIN2_4") (pintype "bidirectional"))
    )
    (net (code "28") (name "/DVL_HRTS") (class "Default")
      (node (ref "5.6") (pin "P$5") (pinfunction "P$3_P$5") (pintype "bidirectional"))
      (node (ref "5.6") (pin "P$6") (pinfunction "P$3_P$6") (pintype "bidirectional"))
      (node (ref "DVL_TTL-TO-RS232") (pin "1") (pinfunction "DOUT3_1") (pintype "bidirectional"))
    )
    (net (code "29") (name "/DVL_HRX") (class "Default")
      (node (ref "5.6") (pin "P$1") (pinfunction "P$1_P$1") (pintype "bidirectional"))
      (node (ref "5.6") (pin "P$2") (pinfunction "P$1_P$2") (pintype "bidirectional"))
      (node (ref "DVL_TTL-TO-RS232") (pin "9") (pinfunction "RIN1_9") (pintype "bidirectional"))
    )
    (net (code "30") (name "/DVL_HRXD") (class "Default")
      (node (ref "DVL_HOST_FTDI") (pin "2") (pinfunction "RXD_2") (pintype "input"))
      (node (ref "DVL_TTL-TO-RS232") (pin "8") (pinfunction "ROUT1_8") (pintype "bidirectional"))
    )
    (net (code "31") (name "/DVL_HTX") (class "Default")
      (node (ref "5.6") (pin "P$3") (pinfunction "P$2_P$3") (pintype "bidirectional"))
      (node (ref "5.6") (pin "P$4") (pinfunction "P$2_P$4") (pintype "bidirectional"))
      (node (ref "DVL_TTL-TO-RS232") (pin "2") (pinfunction "DOUT1_2") (pintype "bidirectional"))
    )
    (net (code "32") (name "/DVL_HTXD") (class "Default")
      (node (ref "DVL_HOST_FTDI") (pin "30") (pinfunction "TXD_30") (pintype "output"))
      (node (ref "DVL_TTL-TO-RS232") (pin "7") (pinfunction "DIN1_7") (pintype "bidirectional"))
    )
    (net (code "33") (name "/DVL_HUSB+") (class "Default")
      (node (ref "DVL_HOST_FTDI") (pin "14") (pinfunction "USBDP_14") (pintype "bidirectional"))
      (node (ref "DVL_USB_HUB") (pin "P$3") (pinfunction "USBDP_DN2_P$3") (pintype "bidirectional"))
    )
    (net (code "34") (name "/DVL_HUSB-") (class "Default")
      (node (ref "DVL_HOST_FTDI") (pin "15") (pinfunction "USBDM_15") (pintype "bidirectional"))
      (node (ref "DVL_USB_HUB") (pin "P$2") (pinfunction "USBDM_DN2_P$2") (pintype "bidirectional"))
    )
    (net (code "35") (name "/DVL_H~{CTS}") (class "Default")
      (node (ref "DVL_HOST_FTDI") (pin "8") (pinfunction "~{CTS}_8") (pintype "input"))
      (node (ref "DVL_TTL-TO-RS232") (pin "5") (pinfunction "ROUT2_5") (pintype "bidirectional"))
    )
    (net (code "36") (name "/DVL_H~{RTS}") (class "Default")
      (node (ref "DVL_HOST_FTDI") (pin "32") (pinfunction "~{RTS}_32") (pintype "output"))
      (node (ref "DVL_TTL-TO-RS232") (pin "20") (pinfunction "DIN3_20") (pintype "bidirectional"))
    )
    (net (code "37") (name "/DVL_SCTS") (class "Default")
      (node (ref "5.7") (pin "P$10") (pinfunction "P$5_P$10") (pintype "bidirectional"))
      (node (ref "5.7") (pin "P$9") (pinfunction "P$5_P$9") (pintype "bidirectional"))
      (node (ref "DVL_TTL-TO-RS232") (pin "23") (pinfunction "RIN4_23") (pintype "bidirectional"))
    )
    (net (code "38") (name "/DVL_SRTS") (class "Default")
      (node (ref "5.5") (pin "P$1") (pinfunction "P$1_P$1") (pintype "bidirectional"))
      (node (ref "5.5") (pin "P$2") (pinfunction "P$1_P$2") (pintype "bidirectional"))
      (node (ref "DVL_TTL-TO-RS232") (pin "28") (pinfunction "DOUT4_28") (pintype "bidirectional"))
    )
    (net (code "39") (name "/DVL_SRX") (class "Default")
      (node (ref "5.6") (pin "P$10") (pinfunction "P$5_P$10") (pintype "bidirectional"))
      (node (ref "5.6") (pin "P$9") (pinfunction "P$5_P$9") (pintype "bidirectional"))
      (node (ref "DVL_TTL-TO-RS232") (pin "27") (pinfunction "RIN3_27") (pintype "bidirectional"))
    )
    (net (code "40") (name "/DVL_SRXD") (class "Default")
      (node (ref "DVL_SLAVE_FTDI") (pin "2") (pinfunction "RXD_2") (pintype "input"))
      (node (ref "DVL_TTL-TO-RS232") (pin "26") (pinfunction "ROUT3_26") (pintype "bidirectional"))
    )
    (net (code "41") (name "/DVL_STX") (class "Default")
      (node (ref "5.4") (pin "P$1") (pinfunction "P$1_P$1") (pintype "bidirectional"))
      (node (ref "5.4") (pin "P$2") (pinfunction "P$1_P$2") (pintype "bidirectional"))
      (node (ref "DVL_TTL-TO-RS232") (pin "3") (pinfunction "DOUT2_3") (pintype "bidirectional"))
    )
    (net (code "42") (name "/DVL_STXD") (class "Default")
      (node (ref "DVL_SLAVE_FTDI") (pin "30") (pinfunction "TXD_30") (pintype "output"))
      (node (ref "DVL_TTL-TO-RS232") (pin "6") (pinfunction "DIN2_6") (pintype "bidirectional"))
    )
    (net (code "43") (name "/DVL_SUSB+") (class "Default")
      (node (ref "DVL_SLAVE_FTDI") (pin "14") (pinfunction "USBDP_14") (pintype "bidirectional"))
      (node (ref "DVL_USB_HUB") (pin "P$1") (pinfunction "USBDP_DN1_P$1") (pintype "bidirectional"))
    )
    (net (code "44") (name "/DVL_SUSB-") (class "Default")
      (node (ref "DVL_SLAVE_FTDI") (pin "15") (pinfunction "USBDM_15") (pintype "bidirectional"))
      (node (ref "DVL_USB_HUB") (pin "P$28") (pinfunction "USBDM_DN1_P$28") (pintype "bidirectional"))
    )
    (net (code "45") (name "/DVL_S~{CTS}") (class "Default")
      (node (ref "DVL_SLAVE_FTDI") (pin "8") (pinfunction "~{CTS}_8") (pintype "input"))
      (node (ref "DVL_TTL-TO-RS232") (pin "22") (pinfunction "ROUT4_22") (pintype "bidirectional"))
    )
    (net (code "46") (name "/DVL_S~{RTS}") (class "Default")
      (node (ref "DVL_SLAVE_FTDI") (pin "32") (pinfunction "~{RTS}_32") (pintype "output"))
      (node (ref "DVL_TTL-TO-RS232") (pin "21") (pinfunction "DIN4_21") (pintype "bidirectional"))
    )
    (net (code "47") (name "/DVL_USB+") (class "Default")
      (node (ref "DVL_USB_HUB") (pin "P$22") (pinfunction "USBDP_UP_P$22") (pintype "bidirectional"))
    )
    (net (code "48") (name "/DVL_USB-") (class "Default")
      (node (ref "DVL_USB_HUB") (pin "P$21") (pinfunction "USBDM_UP_P$21") (pintype "bidirectional"))
    )
    (net (code "49") (name "/FLEX_USB_1+\\") (class "Default")
      (node (ref "JP1") (pin "17") (pinfunction "P$17_17") (pintype "bidirectional"))
      (node (ref "JP2") (pin "17") (pinfunction "P$17_17") (pintype "bidirectional"))
      (node (ref "JP3") (pin "17") (pinfunction "P$17_17") (pintype "bidirectional"))
      (node (ref "JP4") (pin "17") (pinfunction "P$17_17") (pintype "bidirectional"))
    )
    (net (code "50") (name "/FLEX_USB_1-") (class "Default")
      (node (ref "JP1") (pin "16") (pinfunction "P$16_16") (pintype "bidirectional"))
      (node (ref "JP2") (pin "16") (pinfunction "P$16_16") (pintype "bidirectional"))
      (node (ref "JP3") (pin "16") (pinfunction "P$16_16") (pintype "bidirectional"))
      (node (ref "JP4") (pin "16") (pinfunction "P$16_16") (pintype "bidirectional"))
    )
    (net (code "51") (name "/FLEX_USB_2+") (class "Default")
      (node (ref "JP1") (pin "14") (pinfunction "P$14_14") (pintype "bidirectional"))
      (node (ref "JP2") (pin "14") (pinfunction "P$14_14") (pintype "bidirectional"))
      (node (ref "JP3") (pin "14") (pinfunction "P$14_14") (pintype "bidirectional"))
      (node (ref "JP4") (pin "14") (pinfunction "P$14_14") (pintype "bidirectional"))
    )
    (net (code "52") (name "/FLEX_USB_2-") (class "Default")
      (node (ref "JP1") (pin "13") (pinfunction "P$13_13") (pintype "bidirectional"))
      (node (ref "JP2") (pin "13") (pinfunction "P$13_13") (pintype "bidirectional"))
      (node (ref "JP3") (pin "13") (pinfunction "P$13_13") (pintype "bidirectional"))
      (node (ref "JP4") (pin "13") (pinfunction "P$13_13") (pintype "bidirectional"))
    )
    (net (code "53") (name "/GND") (class "Default")
      (node (ref "4PIN_5") (pin "P$1") (pinfunction "P$1_P$1") (pintype "bidirectional"))
      (node (ref "4PIN_5") (pin "P$2") (pinfunction "P$2_P$2") (pintype "bidirectional"))
      (node (ref "4PIN_5") (pin "P$3") (pinfunction "P$3_P$3") (pintype "bidirectional"))
      (node (ref "4PIN_5") (pin "P$4") (pinfunction "P$4_P$4") (pintype "bidirectional"))
      (node (ref "4PIN_6") (pin "P$1") (pinfunction "P$1_P$1") (pintype "bidirectional"))
      (node (ref "4PIN_6") (pin "P$2") (pinfunction "P$2_P$2") (pintype "bidirectional"))
      (node (ref "4PIN_6") (pin "P$3") (pinfunction "P$3_P$3") (pintype "bidirectional"))
      (node (ref "4PIN_6") (pin "P$4") (pinfunction "P$4_P$4") (pintype "bidirectional"))
      (node (ref "5.0") (pin "P$10") (pinfunction "P$5_P$10") (pintype "bidirectional"))
      (node (ref "5.0") (pin "P$3") (pinfunction "P$2_P$3") (pintype "bidirectional"))
      (node (ref "5.0") (pin "P$4") (pinfunction "P$2_P$4") (pintype "bidirectional"))
      (node (ref "5.0") (pin "P$5") (pinfunction "P$3_P$5") (pintype "bidirectional"))
      (node (ref "5.0") (pin "P$6") (pinfunction "P$3_P$6") (pintype "bidirectional"))
      (node (ref "5.0") (pin "P$7") (pinfunction "P$4_P$7") (pintype "bidirectional"))
      (node (ref "5.0") (pin "P$8") (pinfunction "P$4_P$8") (pintype "bidirectional"))
      (node (ref "5.0") (pin "P$9") (pinfunction "P$5_P$9") (pintype "bidirectional"))
      (node (ref "5.2") (pin "P$10") (pinfunction "P$5_P$10") (pintype "bidirectional"))
      (node (ref "5.2") (pin "P$9") (pinfunction "P$5_P$9") (pintype "bidirectional"))
      (node (ref "5.3") (pin "P$10") (pinfunction "P$5_P$10") (pintype "bidirectional"))
      (node (ref "5.3") (pin "P$9") (pinfunction "P$5_P$9") (pintype "bidirectional"))
      (node (ref "5.7") (pin "P$5") (pinfunction "P$3_P$5") (pintype "bidirectional"))
      (node (ref "5.7") (pin "P$6") (pinfunction "P$3_P$6") (pintype "bidirectional"))
      (node (ref "BATTERY-MUX") (pin "P$1") (pinfunction "A0_P$1") (pintype "bidirectional"))
      (node (ref "BATTERY-MUX") (pin "P$13") (pinfunction "A2_P$13") (pintype "bidirectional"))
      (node (ref "BATTERY-MUX") (pin "P$2") (pinfunction "A1_P$2") (pintype "bidirectional"))
      (node (ref "BATTERY-MUX") (pin "P$8") (pinfunction "VSS_P$8") (pintype "bidirectional"))
      (node (ref "C10") (pin "2") (pinfunction "2_2") (pintype "passive"))
      (node (ref "C11") (pin "2") (pinfunction "2_2") (pintype "passive"))
      (node (ref "C12") (pin "2") (pinfunction "2_2") (pintype "passive"))
      (node (ref "C13") (pin "2") (pinfunction "2_2") (pintype "passive"))
      (node (ref "C14") (pin "2") (pinfunction "2_2") (pintype "passive"))
      (node (ref "C15") (pin "2") (pinfunction "2_2") (pintype "passive"))
      (node (ref "C16") (pin "2") (pinfunction "2_2") (pintype "passive"))
      (node (ref "C19") (pin "1") (pinfunction "1_1") (pintype "passive"))
      (node (ref "C2") (pin "2") (pinfunction "2_2") (pintype "passive"))
      (node (ref "C21") (pin "2") (pinfunction "2_2") (pintype "passive"))
      (node (ref "C22") (pin "2") (pinfunction "2_2") (pintype "passive"))
      (node (ref "C25") (pin "2") (pinfunction "2_2") (pintype "passive"))
      (node (ref "C26") (pin "2") (pinfunction "2_2") (pintype "passive"))
      (node (ref "C27") (pin "2") (pinfunction "2_2") (pintype "passive"))
      (node (ref "C3") (pin "2") (pinfunction "2_2") (pintype "passive"))
      (node (ref "C4") (pin "2") (pinfunction "2_2") (pintype "passive"))
      (node (ref "C5") (pin "2") (pinfunction "2_2") (pintype "passive"))
      (node (ref "C6") (pin "2") (pinfunction "2_2") (pintype "passive"))
      (node (ref "C7") (pin "2") (pinfunction "2_2") (pintype "passive"))
      (node (ref "C8") (pin "2") (pinfunction "2_2") (pintype "passive"))
      (node (ref "C9") (pin "2") (pinfunction "2_2") (pintype "passive"))
      (node (ref "DVL_HOST_FTDI") (pin "17") (pinfunction "GND_17") (pintype "power_in"))
      (node (ref "DVL_HOST_FTDI") (pin "20") (pinfunction "GND_20") (pintype "power_in"))
      (node (ref "DVL_HOST_FTDI") (pin "24") (pinfunction "GND_24") (pintype "power_in"))
      (node (ref "DVL_HOST_FTDI") (pin "26") (pinfunction "TEST_26") (pintype "input"))
      (node (ref "DVL_HOST_FTDI") (pin "4") (pinfunction "GND_4") (pintype "power_in"))
      (node (ref "DVL_SLAVE_FTDI") (pin "17") (pinfunction "GND_17") (pintype "power_in"))
      (node (ref "DVL_SLAVE_FTDI") (pin "20") (pinfunction "GND_20") (pintype "power_in"))
      (node (ref "DVL_SLAVE_FTDI") (pin "24") (pinfunction "GND_24") (pintype "power_in"))
      (node (ref "DVL_SLAVE_FTDI") (pin "26") (pinfunction "TEST_26") (pintype "input"))
      (node (ref "DVL_SLAVE_FTDI") (pin "4") (pinfunction "GND_4") (pintype "power_in"))
      (node (ref "DVL_TTL-TO-RS232") (pin "10") (pinfunction "GND_10") (pintype "bidirectional"))
      (node (ref "DVL_USB_HUB") (pin "P$11") (pinfunction "PRTPWR2_P$11") (pintype "bidirectional"))
      (node (ref "DVL_USB_HUB") (pin "P$15") (pinfunction "VSS_P$15") (pintype "bidirectional"))
      (node (ref "DVL_USB_HUB") (pin "P$7") (pinfunction "PRTPWR1_P$7") (pintype "bidirectional"))
      (node (ref "IMU_FTDI") (pin "17") (pinfunction "GND_17") (pintype "power_in"))
      (node (ref "IMU_FTDI") (pin "20") (pinfunction "GND_20") (pintype "power_in"))
      (node (ref "IMU_FTDI") (pin "24") (pinfunction "GND_24") (pintype "power_in"))
      (node (ref "IMU_FTDI") (pin "26") (pinfunction "TEST_26") (pintype "input"))
      (node (ref "IMU_FTDI") (pin "4") (pinfunction "GND_4") (pintype "power_in"))
      (node (ref "IMU_TTL-TO-RS422") (pin "P$14") (pinfunction "GND_P$14") (pintype "bidirectional"))
      (node (ref "IMU_TTL-TO-RS422") (pin "P$15") (pinfunction "232/~{422}_P$15") (pintype "bidirectional"))
      (node (ref "IMU_TTL-TO-RS422") (pin "P$18") (pinfunction "GND_P$18") (pintype "bidirectional"))
      (node (ref "JP1") (pin "12") (pinfunction "P$12_12") (pintype "bidirectional"))
      (node (ref "JP1") (pin "15") (pinfunction "P$15_15") (pintype "bidirectional"))
      (node (ref "JP1") (pin "18") (pinfunction "P$18_18") (pintype "bidirectional"))
      (node (ref "JP1") (pin "24") (pinfunction "P$24_24") (pintype "bidirectional"))
      (node (ref "JP1") (pin "33") (pinfunction "P$33_33") (pintype "bidirectional"))
      (node (ref "JP1") (pin "34") (pinfunction "P$34_34") (pintype "bidirectional"))
      (node (ref "JP1") (pin "36") (pinfunction "P$36_36") (pintype "bidirectional"))
      (node (ref "JP1") (pin "37") (pinfunction "P$37_37") (pintype "bidirectional"))
      (node (ref "JP1") (pin "39") (pinfunction "P$39_39") (pintype "bidirectional"))
      (node (ref "JP1") (pin "4") (pinfunction "P$4_4") (pintype "bidirectional"))
      (node (ref "JP1") (pin "44") (pinfunction "P$44_44") (pintype "bidirectional"))
      (node (ref "JP1") (pin "64") (pinfunction "P$64_64") (pintype "bidirectional"))
      (node (ref "JP1") (pin "P2,1") (pinfunction "POWER2_P2,1") (pintype "bidirectional"))
      (node (ref "JP1") (pin "P2,2") (pinfunction "POWER2_P2,2") (pintype "bidirectional"))
      (node (ref "JP1") (pin "P2,3") (pinfunction "POWER2_P2,3") (pintype "bidirectional"))
      (node (ref "JP1") (pin "P2,4") (pinfunction "POWER2_P2,4") (pintype "bidirectional"))
      (node (ref "JP1") (pin "P2,5") (pinfunction "POWER2_P2,5") (pintype "bidirectional"))
      (node (ref "JP1") (pin "P2,6") (pinfunction "POWER2_P2,6") (pintype "bidirectional"))
      (node (ref "JP2") (pin "12") (pinfunction "P$12_12") (pintype "bidirectional"))
      (node (ref "JP2") (pin "15") (pinfunction "P$15_15") (pintype "bidirectional"))
      (node (ref "JP2") (pin "18") (pinfunction "P$18_18") (pintype "bidirectional"))
      (node (ref "JP2") (pin "24") (pinfunction "P$24_24") (pintype "bidirectional"))
      (node (ref "JP2") (pin "33") (pinfunction "P$33_33") (pintype "bidirectional"))
      (node (ref "JP2") (pin "34") (pinfunction "P$34_34") (pintype "bidirectional"))
      (node (ref "JP2") (pin "36") (pinfunction "P$36_36") (pintype "bidirectional"))
      (node (ref "JP2") (pin "37") (pinfunction "P$37_37") (pintype "bidirectional"))
      (node (ref "JP2") (pin "39") (pinfunction "P$39_39") (pintype "bidirectional"))
      (node (ref "JP2") (pin "4") (pinfunction "P$4_4") (pintype "bidirectional"))
      (node (ref "JP2") (pin "44") (pinfunction "P$44_44") (pintype "bidirectional"))
      (node (ref "JP2") (pin "64") (pinfunction "P$64_64") (pintype "bidirectional"))
      (node (ref "JP2") (pin "P2,1") (pinfunction "POWER2_P2,1") (pintype "bidirectional"))
      (node (ref "JP2") (pin "P2,2") (pinfunction "POWER2_P2,2") (pintype "bidirectional"))
      (node (ref "JP2") (pin "P2,3") (pinfunction "POWER2_P2,3") (pintype "bidirectional"))
      (node (ref "JP2") (pin "P2,4") (pinfunction "POWER2_P2,4") (pintype "bidirectional"))
      (node (ref "JP2") (pin "P2,5") (pinfunction "POWER2_P2,5") (pintype "bidirectional"))
      (node (ref "JP2") (pin "P2,6") (pinfunction "POWER2_P2,6") (pintype "bidirectional"))
      (node (ref "JP3") (pin "12") (pinfunction "P$12_12") (pintype "bidirectional"))
      (node (ref "JP3") (pin "15") (pinfunction "P$15_15") (pintype "bidirectional"))
      (node (ref "JP3") (pin "18") (pinfunction "P$18_18") (pintype "bidirectional"))
      (node (ref "JP3") (pin "24") (pinfunction "P$24_24") (pintype "bidirectional"))
      (node (ref "JP3") (pin "33") (pinfunction "P$33_33") (pintype "bidirectional"))
      (node (ref "JP3") (pin "34") (pinfunction "P$34_34") (pintype "bidirectional"))
      (node (ref "JP3") (pin "36") (pinfunction "P$36_36") (pintype "bidirectional"))
      (node (ref "JP3") (pin "37") (pinfunction "P$37_37") (pintype "bidirectional"))
      (node (ref "JP3") (pin "39") (pinfunction "P$39_39") (pintype "bidirectional"))
      (node (ref "JP3") (pin "4") (pinfunction "P$4_4") (pintype "bidirectional"))
      (node (ref "JP3") (pin "44") (pinfunction "P$44_44") (pintype "bidirectional"))
      (node (ref "JP3") (pin "64") (pinfunction "P$64_64") (pintype "bidirectional"))
      (node (ref "JP3") (pin "P2,1") (pinfunction "POWER2_P2,1") (pintype "bidirectional"))
      (node (ref "JP3") (pin "P2,2") (pinfunction "POWER2_P2,2") (pintype "bidirectional"))
      (node (ref "JP3") (pin "P2,3") (pinfunction "POWER2_P2,3") (pintype "bidirectional"))
      (node (ref "JP3") (pin "P2,4") (pinfunction "POWER2_P2,4") (pintype "bidirectional"))
      (node (ref "JP3") (pin "P2,5") (pinfunction "POWER2_P2,5") (pintype "bidirectional"))
      (node (ref "JP3") (pin "P2,6") (pinfunction "POWER2_P2,6") (pintype "bidirectional"))
      (node (ref "JP4") (pin "12") (pinfunction "P$12_12") (pintype "bidirectional"))
      (node (ref "JP4") (pin "15") (pinfunction "P$15_15") (pintype "bidirectional"))
      (node (ref "JP4") (pin "18") (pinfunction "P$18_18") (pintype "bidirectional"))
      (node (ref "JP4") (pin "24") (pinfunction "P$24_24") (pintype "bidirectional"))
      (node (ref "JP4") (pin "33") (pinfunction "P$33_33") (pintype "bidirectional"))
      (node (ref "JP4") (pin "34") (pinfunction "P$34_34") (pintype "bidirectional"))
      (node (ref "JP4") (pin "36") (pinfunction "P$36_36") (pintype "bidirectional"))
      (node (ref "JP4") (pin "37") (pinfunction "P$37_37") (pintype "bidirectional"))
      (node (ref "JP4") (pin "39") (pinfunction "P$39_39") (pintype "bidirectional"))
      (node (ref "JP4") (pin "4") (pinfunction "P$4_4") (pintype "bidirectional"))
      (node (ref "JP4") (pin "44") (pinfunction "P$44_44") (pintype "bidirectional"))
      (node (ref "JP4") (pin "64") (pinfunction "P$64_64") (pintype "bidirectional"))
      (node (ref "JP4") (pin "P2,1") (pinfunction "POWER2_P2,1") (pintype "bidirectional"))
      (node (ref "JP4") (pin "P2,2") (pinfunction "POWER2_P2,2") (pintype "bidirectional"))
      (node (ref "JP4") (pin "P2,3") (pinfunction "POWER2_P2,3") (pintype "bidirectional"))
      (node (ref "JP4") (pin "P2,4") (pinfunction "POWER2_P2,4") (pintype "bidirectional"))
      (node (ref "JP4") (pin "P2,5") (pinfunction "POWER2_P2,5") (pintype "bidirectional"))
      (node (ref "JP4") (pin "P2,6") (pinfunction "POWER2_P2,6") (pintype "bidirectional"))
      (node (ref "R10") (pin "1") (pinfunction "1_1") (pintype "passive"))
      (node (ref "R12") (pin "1") (pinfunction "1_1") (pintype "passive"))
      (node (ref "R13") (pin "2") (pinfunction "2_2") (pintype "passive"))
      (node (ref "R14") (pin "2") (pinfunction "2_2") (pintype "passive"))
      (node (ref "R15") (pin "2") (pinfunction "2_2") (pintype "passive"))
      (node (ref "SPI_LEDS") (pin "P$5") (pinfunction "P$5_P$5") (pintype "bidirectional"))
      (node (ref "SYS-GND_0") (pin "P$1") (pinfunction "P$1_P$1") (pintype "bidirectional"))
      (node (ref "SYS-GND_0") (pin "P$2") (pinfunction "P$2_P$2") (pintype "bidirectional"))
      (node (ref "SYS-GND_1") (pin "P$1") (pinfunction "P$1_P$1") (pintype "bidirectional"))
      (node (ref "SYS-GND_1") (pin "P$2") (pinfunction "P$2_P$2") (pintype "bidirectional"))
      (node (ref "SYS-GND_2") (pin "P$1") (pinfunction "P$1_P$1") (pintype "bidirectional"))
      (node (ref "SYS-GND_2") (pin "P$2") (pinfunction "P$2_P$2") (pintype "bidirectional"))
      (node (ref "SYS-GND_3") (pin "P$1") (pinfunction "P$1_P$1") (pintype "bidirectional"))
      (node (ref "SYS-GND_3") (pin "P$2") (pinfunction "P$2_P$2") (pintype "bidirectional"))
      (node (ref "U$10") (pin "P$1") (pinfunction "GND_P$1") (pintype "bidirectional"))
      (node (ref "U$11") (pin "P$1") (pinfunction "GND_P$1") (pintype "bidirectional"))
      (node (ref "U$12") (pin "P$1") (pinfunction "GND_P$1") (pintype "bidirectional"))
      (node (ref "U$13") (pin "P$1") (pinfunction "GND_P$1") (pintype "bidirectional"))
      (node (ref "U$14") (pin "P$1") (pinfunction "GND_P$1") (pintype "bidirectional"))
      (node (ref "U$2") (pin "P$1") (pinfunction "GND_P$1") (pintype "bidirectional"))
      (node (ref "U$3") (pin "P$1") (pinfunction "GND_P$1") (pintype "bidirectional"))
      (node (ref "U$4") (pin "P$1") (pinfunction "GND_P$1") (pintype "bidirectional"))
      (node (ref "U$5") (pin "P$1") (pinfunction "GND_P$1") (pintype "bidirectional"))
      (node (ref "U$6") (pin "P$1") (pinfunction "GND_P$1") (pintype "bidirectional"))
      (node (ref "U$7") (pin "P$1") (pinfunction "GND_P$1") (pintype "bidirectional"))
      (node (ref "U$8") (pin "P$1") (pinfunction "GND_P$1") (pintype "bidirectional"))
      (node (ref "U$9") (pin "P$1") (pinfunction "GND_P$1") (pintype "bidirectional"))
    )
    (net (code "54") (name "/GND\\") (class "Default")
      (node (ref "DVL_USB_HUB") (pin "P$29") (pinfunction "GND_P$29") (pintype "bidirectional"))
      (node (ref "JP1") (pin "40") (pinfunction "P$40_40") (pintype "bidirectional"))
      (node (ref "JP2") (pin "40") (pinfunction "P$40_40") (pintype "bidirectional"))
      (node (ref "JP3") (pin "40") (pinfunction "P$40_40") (pintype "bidirectional"))
      (node (ref "JP4") (pin "40") (pinfunction "P$40_40") (pintype "bidirectional"))
    )
    (net (code "55") (name "/GPIO_0") (class "Default")
      (node (ref "JP1") (pin "35") (pinfunction "P$35_35") (pintype "bidirectional"))
      (node (ref "JP2") (pin "35") (pinfunction "P$35_35") (pintype "bidirectional"))
      (node (ref "JP3") (pin "35") (pinfunction "P$35_35") (pintype "bidirectional"))
      (node (ref "JP4") (pin "35") (pinfunction "P$35_35") (pintype "bidirectional"))
    )
    (net (code "56") (name "/GPIO_1") (class "Default")
      (node (ref "JP1") (pin "38") (pinfunction "P$38_38") (pintype "bidirectional"))
      (node (ref "JP2") (pin "38") (pinfunction "P$38_38") (pintype "bidirectional"))
      (node (ref "JP3") (pin "38") (pinfunction "P$38_38") (pintype "bidirectional"))
      (node (ref "JP4") (pin "38") (pinfunction "P$38_38") (pintype "bidirectional"))
    )
    (net (code "57") (name "/GPIO_2") (class "Default")
      (node (ref "JP1") (pin "11") (pinfunction "P$11_11") (pintype "bidirectional"))
      (node (ref "JP2") (pin "11") (pinfunction "P$11_11") (pintype "bidirectional"))
      (node (ref "JP3") (pin "11") (pinfunction "P$11_11") (pintype "bidirectional"))
      (node (ref "JP4") (pin "11") (pinfunction "P$11_11") (pintype "bidirectional"))
    )
    (net (code "58") (name "/GPIO_3") (class "Default")
      (node (ref "JP1") (pin "57") (pinfunction "P$57_57") (pintype "bidirectional"))
      (node (ref "JP2") (pin "57") (pinfunction "P$57_57") (pintype "bidirectional"))
      (node (ref "JP3") (pin "57") (pinfunction "P$57_57") (pintype "bidirectional"))
      (node (ref "JP4") (pin "57") (pinfunction "P$57_57") (pintype "bidirectional"))
    )
    (net (code "59") (name "/GPIO_4") (class "Default")
      (node (ref "JP1") (pin "58") (pinfunction "P$58_58") (pintype "bidirectional"))
      (node (ref "JP2") (pin "58") (pinfunction "P$58_58") (pintype "bidirectional"))
      (node (ref "JP3") (pin "58") (pinfunction "P$58_58") (pintype "bidirectional"))
      (node (ref "JP4") (pin "58") (pinfunction "P$58_58") (pintype "bidirectional"))
    )
    (net (code "60") (name "/IMUT_USB-") (class "Default")
      (node (ref "IMU_FTDI") (pin "15") (pinfunction "USBDM_15") (pintype "bidirectional"))
    )
    (net (code "61") (name "/IMU_RX-A") (class "Default")
      (node (ref "IMU_TTL-TO-RS422") (pin "P$9") (pinfunction "R1-IN/(A)_P$9") (pintype "bidirectional"))
    )
    (net (code "62") (name "/IMU_RX-B") (class "Default")
      (node (ref "IMU_TTL-TO-RS422") (pin "P$8") (pinfunction "R1-IN(B)_P$8") (pintype "bidirectional"))
    )
    (net (code "63") (name "/IMU_RXD") (class "Default")
      (node (ref "IMU_FTDI") (pin "2") (pinfunction "RXD_2") (pintype "input"))
      (node (ref "IMU_TTL-TO-RS422") (pin "P$17") (pinfunction "R1-OUT_P$17") (pintype "bidirectional"))
    )
    (net (code "64") (name "/IMU_USB+") (class "Default")
      (node (ref "IMU_FTDI") (pin "14") (pinfunction "USBDP_14") (pintype "bidirectional"))
    )
    (net (code "65") (name "/MISO") (class "Default")
      (node (ref "JP1") (pin "51") (pinfunction "P$51_51") (pintype "bidirectional"))
      (node (ref "JP2") (pin "51") (pinfunction "P$51_51") (pintype "bidirectional"))
      (node (ref "JP3") (pin "51") (pinfunction "P$51_51") (pintype "bidirectional"))
      (node (ref "JP4") (pin "51") (pinfunction "P$51_51") (pintype "bidirectional"))
      (node (ref "SPI_LEDS") (pin "P$2") (pinfunction "P$2_P$2") (pintype "bidirectional"))
    )
    (net (code "66") (name "/MOSI") (class "Default")
      (node (ref "JP1") (pin "50") (pinfunction "P$50_50") (pintype "bidirectional"))
      (node (ref "JP2") (pin "50") (pinfunction "P$50_50") (pintype "bidirectional"))
      (node (ref "JP3") (pin "50") (pinfunction "P$50_50") (pintype "bidirectional"))
      (node (ref "JP4") (pin "50") (pinfunction "P$50_50") (pintype "bidirectional"))
      (node (ref "SPI_LEDS") (pin "P$3") (pinfunction "P$3_P$3") (pintype "bidirectional"))
    )
    (net (code "67") (name "/PWM_0") (class "Default")
      (node (ref "JP1") (pin "7") (pinfunction "P$7_7") (pintype "bidirectional"))
      (node (ref "JP2") (pin "7") (pinfunction "P$7_7") (pintype "bidirectional"))
      (node (ref "JP3") (pin "7") (pinfunction "P$7_7") (pintype "bidirectional"))
      (node (ref "JP4") (pin "7") (pinfunction "P$7_7") (pintype "bidirectional"))
    )
    (net (code "68") (name "/PWM_1") (class "Default")
      (node (ref "JP1") (pin "8") (pinfunction "P$8_8") (pintype "bidirectional"))
      (node (ref "JP2") (pin "8") (pinfunction "P$8_8") (pintype "bidirectional"))
      (node (ref "JP3") (pin "8") (pinfunction "P$8_8") (pintype "bidirectional"))
      (node (ref "JP4") (pin "8") (pinfunction "P$8_8") (pintype "bidirectional"))
    )
    (net (code "69") (name "/RTS_0") (class "Default")
      (node (ref "JP1") (pin "48") (pinfunction "P$48_48") (pintype "bidirectional"))
      (node (ref "JP2") (pin "48") (pinfunction "P$48_48") (pintype "bidirectional"))
      (node (ref "JP3") (pin "48") (pinfunction "P$48_48") (pintype "bidirectional"))
      (node (ref "JP4") (pin "48") (pinfunction "P$48_48") (pintype "bidirectional"))
    )
    (net (code "70") (name "/RTS_1") (class "Default")
      (node (ref "JP1") (pin "32") (pinfunction "P$32_32") (pintype "bidirectional"))
      (node (ref "JP2") (pin "32") (pinfunction "P$32_32") (pintype "bidirectional"))
      (node (ref "JP3") (pin "32") (pinfunction "P$32_32") (pintype "bidirectional"))
      (node (ref "JP4") (pin "32") (pinfunction "P$32_32") (pintype "bidirectional"))
    )
    (net (code "71") (name "/RTS_2") (class "Default")
      (node (ref "JP1") (pin "72") (pinfunction "P$72_72") (pintype "bidirectional"))
      (node (ref "JP2") (pin "72") (pinfunction "P$72_72") (pintype "bidirectional"))
      (node (ref "JP3") (pin "72") (pinfunction "P$72_72") (pintype "bidirectional"))
      (node (ref "JP4") (pin "72") (pinfunction "P$72_72") (pintype "bidirectional"))
    )
    (net (code "72") (name "/RTS_3") (class "Default")
      (node (ref "JP1") (pin "76") (pinfunction "P$76_76") (pintype "bidirectional"))
      (node (ref "JP2") (pin "76") (pinfunction "P$76_76") (pintype "bidirectional"))
      (node (ref "JP3") (pin "76") (pinfunction "P$76_76") (pintype "bidirectional"))
      (node (ref "JP4") (pin "76") (pinfunction "P$76_76") (pintype "bidirectional"))
    )
    (net (code "73") (name "/RTS_4") (class "Default")
      (node (ref "JP1") (pin "80") (pinfunction "P$80_80") (pintype "bidirectional"))
      (node (ref "JP2") (pin "80") (pinfunction "P$80_80") (pintype "bidirectional"))
      (node (ref "JP3") (pin "80") (pinfunction "P$80_80") (pintype "bidirectional"))
      (node (ref "JP4") (pin "80") (pinfunction "P$80_80") (pintype "bidirectional"))
    )
    (net (code "74") (name "/RTS_5") (class "Default")
      (node (ref "5.2") (pin "P$7") (pinfunction "P$4_P$7") (pintype "bidirectional"))
      (node (ref "5.2") (pin "P$8") (pinfunction "P$4_P$8") (pintype "bidirectional"))
      (node (ref "JP1") (pin "68") (pinfunction "P$68_68") (pintype "bidirectional"))
      (node (ref "JP2") (pin "68") (pinfunction "P$68_68") (pintype "bidirectional"))
      (node (ref "JP3") (pin "68") (pinfunction "P$68_68") (pintype "bidirectional"))
      (node (ref "JP4") (pin "68") (pinfunction "P$68_68") (pintype "bidirectional"))
    )
    (net (code "75") (name "/RX_0") (class "Default")
      (node (ref "JP1") (pin "45") (pinfunction "P$45_45") (pintype "bidirectional"))
      (node (ref "JP2") (pin "45") (pinfunction "P$45_45") (pintype "bidirectional"))
      (node (ref "JP3") (pin "45") (pinfunction "P$45_45") (pintype "bidirectional"))
      (node (ref "JP4") (pin "45") (pinfunction "P$45_45") (pintype "bidirectional"))
    )
    (net (code "76") (name "/RX_1") (class "Default")
      (node (ref "JP1") (pin "29") (pinfunction "P$29_29") (pintype "bidirectional"))
      (node (ref "JP2") (pin "29") (pinfunction "P$29_29") (pintype "bidirectional"))
      (node (ref "JP3") (pin "29") (pinfunction "P$29_29") (pintype "bidirectional"))
      (node (ref "JP4") (pin "29") (pinfunction "P$29_29") (pintype "bidirectional"))
    )
    (net (code "77") (name "/RX_2") (class "Default")
      (node (ref "JP1") (pin "69") (pinfunction "P$69_69") (pintype "bidirectional"))
      (node (ref "JP2") (pin "69") (pinfunction "P$69_69") (pintype "bidirectional"))
      (node (ref "JP3") (pin "69") (pinfunction "P$69_69") (pintype "bidirectional"))
      (node (ref "JP4") (pin "69") (pinfunction "P$69_69") (pintype "bidirectional"))
    )
    (net (code "78") (name "/RX_3") (class "Default")
      (node (ref "JP1") (pin "73") (pinfunction "P$73_73") (pintype "bidirectional"))
      (node (ref "JP2") (pin "73") (pinfunction "P$73_73") (pintype "bidirectional"))
      (node (ref "JP3") (pin "73") (pinfunction "P$73_73") (pintype "bidirectional"))
      (node (ref "JP4") (pin "73") (pinfunction "P$73_73") (pintype "bidirectional"))
    )
    (net (code "79") (name "/RX_4") (class "Default")
      (node (ref "JP1") (pin "77") (pinfunction "P$77_77") (pintype "bidirectional"))
      (node (ref "JP2") (pin "77") (pinfunction "P$77_77") (pintype "bidirectional"))
      (node (ref "JP3") (pin "77") (pinfunction "P$77_77") (pintype "bidirectional"))
      (node (ref "JP4") (pin "77") (pinfunction "P$77_77") (pintype "bidirectional"))
    )
    (net (code "80") (name "/RX_5") (class "Default")
      (node (ref "5.2") (pin "P$1") (pinfunction "P$1_P$1") (pintype "bidirectional"))
      (node (ref "5.2") (pin "P$2") (pinfunction "P$1_P$2") (pintype "bidirectional"))
      (node (ref "JP1") (pin "65") (pinfunction "P$65_65") (pintype "bidirectional"))
      (node (ref "JP2") (pin "65") (pinfunction "P$65_65") (pintype "bidirectional"))
      (node (ref "JP3") (pin "65") (pinfunction "P$65_65") (pintype "bidirectional"))
      (node (ref "JP4") (pin "65") (pinfunction "P$65_65") (pintype "bidirectional"))
    )
    (net (code "81") (name "/SCL_0") (class "Default")
      (node (ref "BATTERY-MUX") (pin "P$14") (pinfunction "SCL_P$14") (pintype "bidirectional"))
      (node (ref "JP1") (pin "28") (pinfunction "P$28_28") (pintype "bidirectional"))
      (node (ref "JP2") (pin "28") (pinfunction "P$28_28") (pintype "bidirectional"))
      (node (ref "JP3") (pin "28") (pinfunction "P$28_28") (pintype "bidirectional"))
      (node (ref "JP4") (pin "28") (pinfunction "P$28_28") (pintype "bidirectional"))
    )
    (net (code "82") (name "/SCL_1") (class "Default")
      (node (ref "JP1") (pin "10") (pinfunction "P$10_10") (pintype "bidirectional"))
      (node (ref "JP2") (pin "10") (pinfunction "P$10_10") (pintype "bidirectional"))
      (node (ref "JP3") (pin "10") (pinfunction "P$10_10") (pintype "bidirectional"))
      (node (ref "JP4") (pin "10") (pinfunction "P$10_10") (pintype "bidirectional"))
    )
    (net (code "83") (name "/SCL_2") (class "Default")
      (node (ref "5.4") (pin "P$10") (pinfunction "P$5_P$10") (pintype "bidirectional"))
      (node (ref "5.4") (pin "P$9") (pinfunction "P$5_P$9") (pintype "bidirectional"))
      (node (ref "JP1") (pin "60") (pinfunction "P$60_60") (pintype "bidirectional"))
      (node (ref "JP2") (pin "60") (pinfunction "P$60_60") (pintype "bidirectional"))
      (node (ref "JP3") (pin "60") (pinfunction "P$60_60") (pintype "bidirectional"))
      (node (ref "JP4") (pin "60") (pinfunction "P$60_60") (pintype "bidirectional"))
    )
    (net (code "84") (name "/SCL_3") (class "Default")
      (node (ref "5.3") (pin "P$3") (pinfunction "P$2_P$3") (pintype "bidirectional"))
      (node (ref "5.3") (pin "P$4") (pinfunction "P$2_P$4") (pintype "bidirectional"))
      (node (ref "JP1") (pin "6") (pinfunction "P$6_6") (pintype "bidirectional"))
      (node (ref "JP2") (pin "6") (pinfunction "P$6_6") (pintype "bidirectional"))
      (node (ref "JP3") (pin "6") (pinfunction "P$6_6") (pintype "bidirectional"))
      (node (ref "JP4") (pin "6") (pinfunction "P$6_6") (pintype "bidirectional"))
    )
    (net (code "85") (name "/SDA_0") (class "Default")
      (node (ref "BATTERY-MUX") (pin "P$15") (pinfunction "SDA_P$15") (pintype "bidirectional"))
      (node (ref "JP1") (pin "27") (pinfunction "P$27_27") (pintype "bidirectional"))
      (node (ref "JP2") (pin "27") (pinfunction "P$27_27") (pintype "bidirectional"))
      (node (ref "JP3") (pin "27") (pinfunction "P$27_27") (pintype "bidirectional"))
      (node (ref "JP4") (pin "27") (pinfunction "P$27_27") (pintype "bidirectional"))
    )
    (net (code "86") (name "/SDA_1") (class "Default")
      (node (ref "JP1") (pin "9") (pinfunction "P$9_9") (pintype "bidirectional"))
      (node (ref "JP2") (pin "9") (pinfunction "P$9_9") (pintype "bidirectional"))
      (node (ref "JP3") (pin "9") (pinfunction "P$9_9") (pintype "bidirectional"))
      (node (ref "JP4") (pin "9") (pinfunction "P$9_9") (pintype "bidirectional"))
    )
    (net (code "87") (name "/SDA_2") (class "Default")
      (node (ref "5.5") (pin "P$10") (pinfunction "P$5_P$10") (pintype "bidirectional"))
      (node (ref "5.5") (pin "P$9") (pinfunction "P$5_P$9") (pintype "bidirectional"))
      (node (ref "JP1") (pin "59") (pinfunction "P$59_59") (pintype "bidirectional"))
      (node (ref "JP2") (pin "59") (pinfunction "P$59_59") (pintype "bidirectional"))
      (node (ref "JP3") (pin "59") (pinfunction "P$59_59") (pintype "bidirectional"))
      (node (ref "JP4") (pin "59") (pinfunction "P$59_59") (pintype "bidirectional"))
    )
    (net (code "88") (name "/SDA_3") (class "Default")
      (node (ref "5.3") (pin "P$1") (pinfunction "P$1_P$1") (pintype "bidirectional"))
      (node (ref "5.3") (pin "P$2") (pinfunction "P$1_P$2") (pintype "bidirectional"))
      (node (ref "JP1") (pin "5") (pinfunction "P$5_5") (pintype "bidirectional"))
      (node (ref "JP2") (pin "5") (pinfunction "P$5_5") (pintype "bidirectional"))
      (node (ref "JP3") (pin "5") (pinfunction "P$5_5") (pintype "bidirectional"))
      (node (ref "JP4") (pin "5") (pinfunction "P$5_5") (pintype "bidirectional"))
    )
    (net (code "89") (name "/SHORE_SCL") (class "Default")
      (node (ref "5.4") (pin "P$3") (pinfunction "P$2_P$3") (pintype "bidirectional"))
      (node (ref "5.4") (pin "P$4") (pinfunction "P$2_P$4") (pintype "bidirectional"))
      (node (ref "BATTERY-MUX") (pin "P$5") (pinfunction "SC0_P$5") (pintype "bidirectional"))
    )
    (net (code "90") (name "/SHORE_SDA") (class "Default")
      (node (ref "5.5") (pin "P$3") (pinfunction "P$2_P$3") (pintype "bidirectional"))
      (node (ref "5.5") (pin "P$4") (pinfunction "P$2_P$4") (pintype "bidirectional"))
      (node (ref "BATTERY-MUX") (pin "P$4") (pinfunction "SD0_P$4") (pintype "bidirectional"))
    )
    (net (code "91") (name "/SPI_CLK") (class "Default")
      (node (ref "JP1") (pin "49") (pinfunction "P$49_49") (pintype "bidirectional"))
      (node (ref "JP2") (pin "49") (pinfunction "P$49_49") (pintype "bidirectional"))
      (node (ref "JP3") (pin "49") (pinfunction "P$49_49") (pintype "bidirectional"))
      (node (ref "JP4") (pin "49") (pinfunction "P$49_49") (pintype "bidirectional"))
      (node (ref "SPI_LEDS") (pin "P$4") (pinfunction "P$4_P$4") (pintype "bidirectional"))
    )
    (net (code "92") (name "/TX_0") (class "Default")
      (node (ref "JP1") (pin "46") (pinfunction "P$46_46") (pintype "bidirectional"))
      (node (ref "JP2") (pin "46") (pinfunction "P$46_46") (pintype "bidirectional"))
      (node (ref "JP3") (pin "46") (pinfunction "P$46_46") (pintype "bidirectional"))
      (node (ref "JP4") (pin "46") (pinfunction "P$46_46") (pintype "bidirectional"))
    )
    (net (code "93") (name "/TX_1") (class "Default")
      (node (ref "JP1") (pin "30") (pinfunction "P$30_30") (pintype "bidirectional"))
      (node (ref "JP2") (pin "30") (pinfunction "P$30_30") (pintype "bidirectional"))
      (node (ref "JP3") (pin "30") (pinfunction "P$30_30") (pintype "bidirectional"))
      (node (ref "JP4") (pin "30") (pinfunction "P$30_30") (pintype "bidirectional"))
    )
    (net (code "94") (name "/TX_2") (class "Default")
      (node (ref "JP1") (pin "70") (pinfunction "P$70_70") (pintype "bidirectional"))
      (node (ref "JP2") (pin "70") (pinfunction "P$70_70") (pintype "bidirectional"))
      (node (ref "JP3") (pin "70") (pinfunction "P$70_70") (pintype "bidirectional"))
      (node (ref "JP4") (pin "70") (pinfunction "P$70_70") (pintype "bidirectional"))
    )
    (net (code "95") (name "/TX_3") (class "Default")
      (node (ref "JP1") (pin "74") (pinfunction "P$74_74") (pintype "bidirectional"))
      (node (ref "JP2") (pin "74") (pinfunction "P$74_74") (pintype "bidirectional"))
      (node (ref "JP3") (pin "74") (pinfunction "P$74_74") (pintype "bidirectional"))
      (node (ref "JP4") (pin "74") (pinfunction "P$74_74") (pintype "bidirectional"))
    )
    (net (code "96") (name "/TX_4") (class "Default")
      (node (ref "JP1") (pin "78") (pinfunction "P$78_78") (pintype "bidirectional"))
      (node (ref "JP2") (pin "78") (pinfunction "P$78_78") (pintype "bidirectional"))
      (node (ref "JP3") (pin "78") (pinfunction "P$78_78") (pintype "bidirectional"))
      (node (ref "JP4") (pin "78") (pinfunction "P$78_78") (pintype "bidirectional"))
    )
    (net (code "97") (name "/TX_5") (class "Default")
      (node (ref "5.2") (pin "P$3") (pinfunction "P$2_P$3") (pintype "bidirectional"))
      (node (ref "5.2") (pin "P$4") (pinfunction "P$2_P$4") (pintype "bidirectional"))
      (node (ref "JP1") (pin "66") (pinfunction "P$66_66") (pintype "bidirectional"))
      (node (ref "JP2") (pin "66") (pinfunction "P$66_66") (pintype "bidirectional"))
      (node (ref "JP3") (pin "66") (pinfunction "P$66_66") (pintype "bidirectional"))
      (node (ref "JP4") (pin "66") (pinfunction "P$66_66") (pintype "bidirectional"))
    )
    (net (code "98") (name "/USB_1+") (class "Default")
      (node (ref "JP1") (pin "20") (pinfunction "P$20_20") (pintype "bidirectional"))
    )
    (net (code "99") (name "/USB_1-") (class "Default")
      (node (ref "JP1") (pin "19") (pinfunction "P$19_19") (pintype "bidirectional"))
    )
    (net (code "100") (name "/USB_2+") (class "Default")
      (node (ref "JP2") (pin "20") (pinfunction "P$20_20") (pintype "bidirectional"))
    )
    (net (code "101") (name "/USB_2-") (class "Default")
      (node (ref "JP2") (pin "19") (pinfunction "P$19_19") (pintype "bidirectional"))
    )
    (net (code "102") (name "/USB_3+") (class "Default")
      (node (ref "JP3") (pin "20") (pinfunction "P$20_20") (pintype "bidirectional"))
    )
    (net (code "103") (name "/USB_3-") (class "Default")
      (node (ref "JP3") (pin "19") (pinfunction "P$19_19") (pintype "bidirectional"))
    )
    (net (code "104") (name "/USB_4+") (class "Default")
      (node (ref "JP4") (pin "20") (pinfunction "P$20_20") (pintype "bidirectional"))
    )
    (net (code "105") (name "/USB_4-") (class "Default")
      (node (ref "JP4") (pin "19") (pinfunction "P$19_19") (pintype "bidirectional"))
    )
    (net (code "106") (name "/USB_EXT+") (class "Default")
      (node (ref "5.7") (pin "P$3") (pinfunction "P$2_P$3") (pintype "bidirectional"))
      (node (ref "5.7") (pin "P$4") (pinfunction "P$2_P$4") (pintype "bidirectional"))
    )
    (net (code "107") (name "/USB_EXT-") (class "Default")
      (node (ref "5.7") (pin "P$1") (pinfunction "P$1_P$1") (pintype "bidirectional"))
      (node (ref "5.7") (pin "P$2") (pinfunction "P$1_P$2") (pintype "bidirectional"))
    )
    (net (code "108") (name "/V_BATT") (class "Default")
      (node (ref "4PIN_3") (pin "P$1") (pinfunction "P$1_P$1") (pintype "bidirectional"))
      (node (ref "4PIN_3") (pin "P$2") (pinfunction "P$2_P$2") (pintype "bidirectional"))
      (node (ref "4PIN_3") (pin "P$3") (pinfunction "P$3_P$3") (pintype "bidirectional"))
      (node (ref "4PIN_3") (pin "P$4") (pinfunction "P$4_P$4") (pintype "bidirectional"))
      (node (ref "4PIN_4") (pin "P$1") (pinfunction "P$1_P$1") (pintype "bidirectional"))
      (node (ref "4PIN_4") (pin "P$2") (pinfunction "P$2_P$2") (pintype "bidirectional"))
      (node (ref "4PIN_4") (pin "P$3") (pinfunction "P$3_P$3") (pintype "bidirectional"))
      (node (ref "4PIN_4") (pin "P$4") (pinfunction "P$4_P$4") (pintype "bidirectional"))
      (node (ref "JP1") (pin "P1,1") (pinfunction "POWER1_P1,1") (pintype "bidirectional"))
      (node (ref "JP1") (pin "P1,2") (pinfunction "POWER1_P1,2") (pintype "bidirectional"))
      (node (ref "JP1") (pin "P1,3") (pinfunction "POWER1_P1,3") (pintype "bidirectional"))
      (node (ref "JP1") (pin "P1,4") (pinfunction "POWER1_P1,4") (pintype "bidirectional"))
      (node (ref "JP1") (pin "P1,5") (pinfunction "POWER1_P1,5") (pintype "bidirectional"))
      (node (ref "JP1") (pin "P1,6") (pinfunction "POWER1_P1,6") (pintype "bidirectional"))
      (node (ref "JP2") (pin "P1,1") (pinfunction "POWER1_P1,1") (pintype "bidirectional"))
      (node (ref "JP2") (pin "P1,2") (pinfunction "POWER1_P1,2") (pintype "bidirectional"))
      (node (ref "JP2") (pin "P1,3") (pinfunction "POWER1_P1,3") (pintype "bidirectional"))
      (node (ref "JP2") (pin "P1,4") (pinfunction "POWER1_P1,4") (pintype "bidirectional"))
      (node (ref "JP2") (pin "P1,5") (pinfunction "POWER1_P1,5") (pintype "bidirectional"))
      (node (ref "JP2") (pin "P1,6") (pinfunction "POWER1_P1,6") (pintype "bidirectional"))
      (node (ref "JP3") (pin "P1,1") (pinfunction "POWER1_P1,1") (pintype "bidirectional"))
      (node (ref "JP3") (pin "P1,2") (pinfunction "POWER1_P1,2") (pintype "bidirectional"))
      (node (ref "JP3") (pin "P1,3") (pinfunction "POWER1_P1,3") (pintype "bidirectional"))
      (node (ref "JP3") (pin "P1,4") (pinfunction "POWER1_P1,4") (pintype "bidirectional"))
      (node (ref "JP3") (pin "P1,5") (pinfunction "POWER1_P1,5") (pintype "bidirectional"))
      (node (ref "JP3") (pin "P1,6") (pinfunction "POWER1_P1,6") (pintype "bidirectional"))
      (node (ref "JP4") (pin "P1,1") (pinfunction "POWER1_P1,1") (pintype "bidirectional"))
      (node (ref "JP4") (pin "P1,2") (pinfunction "POWER1_P1,2") (pintype "bidirectional"))
      (node (ref "JP4") (pin "P1,3") (pinfunction "POWER1_P1,3") (pintype "bidirectional"))
      (node (ref "JP4") (pin "P1,4") (pinfunction "POWER1_P1,4") (pintype "bidirectional"))
      (node (ref "JP4") (pin "P1,5") (pinfunction "POWER1_P1,5") (pintype "bidirectional"))
      (node (ref "JP4") (pin "P1,6") (pinfunction "POWER1_P1,6") (pintype "bidirectional"))
    )
    (net (code "109") (name "Net-(CPU_USB_CPU-PadP$1)") (class "Default")
      (node (ref "CPU_USB_CPU") (pin "P$1") (pinfunction "P$1_P$1") (pintype "bidirectional"))
      (node (ref "R2") (pin "1") (pinfunction "1_1") (pintype "passive"))
    )
    (net (code "110") (name "Net-(CPU_USB_CPU-PadP$2)") (class "Default")
      (node (ref "CPU_USB_CPU") (pin "P$2") (pinfunction "P$2_P$2") (pintype "bidirectional"))
      (node (ref "R1") (pin "1") (pinfunction "1_1") (pintype "passive"))
    )
    (net (code "111") (name "Net-(DVL_HOST_FTDI-3V3OUT)") (class "Default")
      (node (ref "C4") (pin "1") (pinfunction "1_1") (pintype "passive"))
      (node (ref "DVL_HOST_FTDI") (pin "16") (pinfunction "3V3OUT_16") (pintype "output"))
    )
    (net (code "112") (name "Net-(DVL_HOST_FTDI-CBUS0)") (class "Default")
      (node (ref "DVL_HOST_FTDI") (pin "22") (pinfunction "CBUS0_22") (pintype "bidirectional"))
      (node (ref "LED1") (pin "C") (pinfunction "C_C") (pintype "passive"))
    )
    (net (code "113") (name "Net-(DVL_HOST_FTDI-CBUS1)") (class "Default")
      (node (ref "DVL_HOST_FTDI") (pin "21") (pinfunction "CBUS1_21") (pintype "bidirectional"))
      (node (ref "LED2") (pin "C") (pinfunction "C_C") (pintype "passive"))
    )
    (net (code "114") (name "Net-(DVL_SLAVE_FTDI-3V3OUT)") (class "Default")
      (node (ref "C8") (pin "1") (pinfunction "1_1") (pintype "passive"))
      (node (ref "DVL_SLAVE_FTDI") (pin "16") (pinfunction "3V3OUT_16") (pintype "output"))
    )
    (net (code "115") (name "Net-(DVL_SLAVE_FTDI-CBUS0)") (class "Default")
      (node (ref "DVL_SLAVE_FTDI") (pin "22") (pinfunction "CBUS0_22") (pintype "bidirectional"))
      (node (ref "LED3") (pin "C") (pinfunction "C_C") (pintype "passive"))
    )
    (net (code "116") (name "Net-(DVL_SLAVE_FTDI-CBUS1)") (class "Default")
      (node (ref "DVL_SLAVE_FTDI") (pin "21") (pinfunction "CBUS1_21") (pintype "bidirectional"))
      (node (ref "LED4") (pin "C") (pinfunction "C_C") (pintype "passive"))
    )
    (net (code "117") (name "Net-(DVL_TTL-TO-RS232-C1+)") (class "Default")
      (node (ref "C18") (pin "1") (pinfunction "1_1") (pintype "passive"))
      (node (ref "DVL_TTL-TO-RS232") (pin "12") (pinfunction "C1+_12") (pintype "bidirectional"))
    )
    (net (code "118") (name "Net-(DVL_TTL-TO-RS232-C1-)") (class "Default")
      (node (ref "C18") (pin "2") (pinfunction "2_2") (pintype "passive"))
      (node (ref "DVL_TTL-TO-RS232") (pin "14") (pinfunction "C1-_14") (pintype "bidirectional"))
    )
    (net (code "119") (name "Net-(DVL_TTL-TO-RS232-C2+)") (class "Default")
      (node (ref "C20") (pin "1") (pinfunction "1_1") (pintype "passive"))
      (node (ref "DVL_TTL-TO-RS232") (pin "15") (pinfunction "C2+_15") (pintype "bidirectional"))
    )
    (net (code "120") (name "Net-(DVL_TTL-TO-RS232-C2-)") (class "Default")
      (node (ref "C20") (pin "2") (pinfunction "2_2") (pintype "passive"))
      (node (ref "DVL_TTL-TO-RS232") (pin "16") (pinfunction "C2-_16") (pintype "bidirectional"))
    )
    (net (code "121") (name "Net-(DVL_TTL-TO-RS232-V+)") (class "Default")
      (node (ref "C17") (pin "1") (pinfunction "1_1") (pintype "passive"))
      (node (ref "DVL_TTL-TO-RS232") (pin "13") (pinfunction "V+_13") (pintype "bidirectional"))
    )
    (net (code "122") (name "Net-(DVL_TTL-TO-RS232-V-)") (class "Default")
      (node (ref "C19") (pin "2") (pinfunction "2_2") (pintype "passive"))
      (node (ref "DVL_TTL-TO-RS232") (pin "17") (pinfunction "V-_17") (pintype "bidirectional"))
    )
    (net (code "123") (name "Net-(DVL_USB_HUB-CRFILT)") (class "Default")
      (node (ref "C27") (pin "1") (pinfunction "1_1") (pintype "passive"))
      (node (ref "DVL_USB_HUB") (pin "P$9") (pinfunction "CRFILT_P$9") (pintype "bidirectional"))
    )
    (net (code "124") (name "Net-(DVL_USB_HUB-HS_IND)") (class "Default")
      (node (ref "DVL_USB_HUB") (pin "P$16") (pinfunction "HS_IND_P$16") (pintype "bidirectional"))
      (node (ref "R10") (pin "2") (pinfunction "2_2") (pintype "passive"))
    )
    (net (code "125") (name "Net-(DVL_USB_HUB-NON_REM1)") (class "Default")
      (node (ref "DVL_USB_HUB") (pin "P$13") (pinfunction "NON_REM1_P$13") (pintype "bidirectional"))
      (node (ref "R15") (pin "1") (pinfunction "1_1") (pintype "passive"))
    )
    (net (code "126") (name "Net-(DVL_USB_HUB-PLLFILT)") (class "Default")
      (node (ref "C26") (pin "1") (pinfunction "1_1") (pintype "passive"))
      (node (ref "DVL_USB_HUB") (pin "P$25") (pinfunction "PLLFILT_P$25") (pintype "bidirectional"))
    )
    (net (code "127") (name "Net-(DVL_USB_HUB-RBIAS)") (class "Default")
      (node (ref "DVL_USB_HUB") (pin "P$26") (pinfunction "RBIAS_P$26") (pintype "bidirectional"))
      (node (ref "R12") (pin "2") (pinfunction "2_2") (pintype "passive"))
    )
    (net (code "128") (name "Net-(DVL_USB_HUB-RESET_N)") (class "Default")
      (node (ref "DVL_USB_HUB") (pin "P$17") (pinfunction "RESET_N_P$17") (pintype "bidirectional"))
      (node (ref "R11") (pin "1") (pinfunction "1_1") (pintype "passive"))
    )
    (net (code "129") (name "Net-(DVL_USB_HUB-SUSP_IND{slash}NON_REM0)") (class "Default")
      (node (ref "DVL_USB_HUB") (pin "P$19") (pinfunction "SUSP_IND/NON_REM0_P$19") (pintype "bidirectional"))
      (node (ref "LED7") (pin "A") (pinfunction "A_A") (pintype "passive"))
      (node (ref "R14") (pin "1") (pinfunction "1_1") (pintype "passive"))
    )
    (net (code "130") (name "Net-(IMU_FTDI-3V3OUT)") (class "Default")
      (node (ref "C12") (pin "1") (pinfunction "1_1") (pintype "passive"))
      (node (ref "IMU_FTDI") (pin "16") (pinfunction "3V3OUT_16") (pintype "output"))
    )
    (net (code "131") (name "Net-(IMU_FTDI-CBUS0)") (class "Default")
      (node (ref "IMU_FTDI") (pin "22") (pinfunction "CBUS0_22") (pintype "bidirectional"))
      (node (ref "LED5") (pin "C") (pinfunction "C_C") (pintype "passive"))
    )
    (net (code "132") (name "Net-(IMU_FTDI-CBUS1)") (class "Default")
      (node (ref "IMU_FTDI") (pin "21") (pinfunction "CBUS1_21") (pintype "bidirectional"))
      (node (ref "LED6") (pin "C") (pinfunction "C_C") (pintype "passive"))
    )
    (net (code "133") (name "Net-(IMU_TTL-TO-RS422-C1+)") (class "Default")
      (node (ref "C23") (pin "1") (pinfunction "1_1") (pintype "passive"))
      (node (ref "IMU_TTL-TO-RS422") (pin "P$2") (pinfunction "C1+_P$2") (pintype "bidirectional"))
    )
    (net (code "134") (name "Net-(IMU_TTL-TO-RS422-C1-)") (class "Default")
      (node (ref "C23") (pin "2") (pinfunction "2_2") (pintype "passive"))
      (node (ref "IMU_TTL-TO-RS422") (pin "P$3") (pinfunction "C1-_P$3") (pintype "bidirectional"))
    )
    (net (code "135") (name "Net-(IMU_TTL-TO-RS422-C2+)") (class "Default")
      (node (ref "C24") (pin "1") (pinfunction "1_1") (pintype "passive"))
      (node (ref "IMU_TTL-TO-RS422") (pin "P$22") (pinfunction "C2+_P$22") (pintype "bidirectional"))
    )
    (net (code "136") (name "Net-(IMU_TTL-TO-RS422-C2-)") (class "Default")
      (node (ref "C24") (pin "2") (pinfunction "2_2") (pintype "passive"))
      (node (ref "IMU_TTL-TO-RS422") (pin "P$23") (pinfunction "C2-_P$23") (pintype "bidirectional"))
    )
    (net (code "137") (name "Net-(IMU_TTL-TO-RS422-V+)") (class "Default")
      (node (ref "C21") (pin "1") (pinfunction "1_1") (pintype "passive"))
      (node (ref "IMU_TTL-TO-RS422") (pin "P$1") (pinfunction "V+_P$1") (pintype "bidirectional"))
    )
    (net (code "138") (name "Net-(IMU_TTL-TO-RS422-V-)") (class "Default")
      (node (ref "C22") (pin "1") (pinfunction "1_1") (pintype "passive"))
      (node (ref "IMU_TTL-TO-RS422") (pin "P$24") (pinfunction "V-_P$24") (pintype "bidirectional"))
    )
    (net (code "139") (name "Net-(LED1-PadA)") (class "Default")
      (node (ref "LED1") (pin "A") (pinfunction "A_A") (pintype "passive"))
      (node (ref "R4") (pin "1") (pinfunction "1_1") (pintype "passive"))
    )
    (net (code "140") (name "Net-(LED2-PadA)") (class "Default")
      (node (ref "LED2") (pin "A") (pinfunction "A_A") (pintype "passive"))
      (node (ref "R5") (pin "1") (pinfunction "1_1") (pintype "passive"))
    )
    (net (code "141") (name "Net-(LED3-PadA)") (class "Default")
      (node (ref "LED3") (pin "A") (pinfunction "A_A") (pintype "passive"))
      (node (ref "R6") (pin "1") (pinfunction "1_1") (pintype "passive"))
    )
    (net (code "142") (name "Net-(LED4-PadA)") (class "Default")
      (node (ref "LED4") (pin "A") (pinfunction "A_A") (pintype "passive"))
      (node (ref "R7") (pin "1") (pinfunction "1_1") (pintype "passive"))
    )
    (net (code "143") (name "Net-(LED5-PadA)") (class "Default")
      (node (ref "LED5") (pin "A") (pinfunction "A_A") (pintype "passive"))
      (node (ref "R8") (pin "1") (pinfunction "1_1") (pintype "passive"))
    )
    (net (code "144") (name "Net-(LED6-PadA)") (class "Default")
      (node (ref "LED6") (pin "A") (pinfunction "A_A") (pintype "passive"))
      (node (ref "R9") (pin "1") (pinfunction "1_1") (pintype "passive"))
    )
    (net (code "145") (name "Net-(LED7-PadC)") (class "Default")
      (node (ref "LED7") (pin "C") (pinfunction "C_C") (pintype "passive"))
      (node (ref "R13") (pin "1") (pinfunction "1_1") (pintype "passive"))
    )
    (net (code "146") (name "unconnected-(2PIN_1-PadP$1)") (class "Default")
      (node (ref "2PIN_1") (pin "P$1") (pinfunction "P$1_P$1") (pintype "bidirectional"))
    )
    (net (code "147") (name "unconnected-(2PIN_1-PadP$2)") (class "Default")
      (node (ref "2PIN_1") (pin "P$2") (pinfunction "P$2_P$2") (pintype "bidirectional"))
    )
    (net (code "148") (name "unconnected-(2PIN_2-PadP$1)") (class "Default")
      (node (ref "2PIN_2") (pin "P$1") (pinfunction "P$1_P$1") (pintype "bidirectional"))
    )
    (net (code "149") (name "unconnected-(2PIN_2-PadP$2)") (class "Default")
      (node (ref "2PIN_2") (pin "P$2") (pinfunction "P$2_P$2") (pintype "bidirectional"))
    )
    (net (code "150") (name "unconnected-(2PIN_3-PadP$1)") (class "Default")
      (node (ref "2PIN_3") (pin "P$1") (pinfunction "P$1_P$1") (pintype "bidirectional"))
    )
    (net (code "151") (name "unconnected-(2PIN_3-PadP$2)") (class "Default")
      (node (ref "2PIN_3") (pin "P$2") (pinfunction "P$2_P$2") (pintype "bidirectional"))
    )
    (net (code "152") (name "unconnected-(2PIN_4-PadP$1)") (class "Default")
      (node (ref "2PIN_4") (pin "P$1") (pinfunction "P$1_P$1") (pintype "bidirectional"))
    )
    (net (code "153") (name "unconnected-(2PIN_4-PadP$2)") (class "Default")
      (node (ref "2PIN_4") (pin "P$2") (pinfunction "P$2_P$2") (pintype "bidirectional"))
    )
    (net (code "154") (name "unconnected-(2PIN_5-PadP$1)") (class "Default")
      (node (ref "2PIN_5") (pin "P$1") (pinfunction "P$1_P$1") (pintype "bidirectional"))
    )
    (net (code "155") (name "unconnected-(2PIN_5-PadP$2)") (class "Default")
      (node (ref "2PIN_5") (pin "P$2") (pinfunction "P$2_P$2") (pintype "bidirectional"))
    )
    (net (code "156") (name "unconnected-(2PIN_6-PadP$1)") (class "Default")
      (node (ref "2PIN_6") (pin "P$1") (pinfunction "P$1_P$1") (pintype "bidirectional"))
    )
    (net (code "157") (name "unconnected-(2PIN_6-PadP$2)") (class "Default")
      (node (ref "2PIN_6") (pin "P$2") (pinfunction "P$2_P$2") (pintype "bidirectional"))
    )
    (net (code "158") (name "unconnected-(4PIN_1-PadP$1)") (class "Default")
      (node (ref "4PIN_1") (pin "P$1") (pinfunction "P$1_P$1") (pintype "bidirectional"))
    )
    (net (code "159") (name "unconnected-(4PIN_1-PadP$2)") (class "Default")
      (node (ref "4PIN_1") (pin "P$2") (pinfunction "P$2_P$2") (pintype "bidirectional"))
    )
    (net (code "160") (name "unconnected-(4PIN_1-PadP$3)") (class "Default")
      (node (ref "4PIN_1") (pin "P$3") (pinfunction "P$3_P$3") (pintype "bidirectional"))
    )
    (net (code "161") (name "unconnected-(4PIN_1-PadP$4)") (class "Default")
      (node (ref "4PIN_1") (pin "P$4") (pinfunction "P$4_P$4") (pintype "bidirectional"))
    )
    (net (code "162") (name "unconnected-(4PIN_2-PadP$1)") (class "Default")
      (node (ref "4PIN_2") (pin "P$1") (pinfunction "P$1_P$1") (pintype "bidirectional"))
    )
    (net (code "163") (name "unconnected-(4PIN_2-PadP$2)") (class "Default")
      (node (ref "4PIN_2") (pin "P$2") (pinfunction "P$2_P$2") (pintype "bidirectional"))
    )
    (net (code "164") (name "unconnected-(4PIN_2-PadP$3)") (class "Default")
      (node (ref "4PIN_2") (pin "P$3") (pinfunction "P$3_P$3") (pintype "bidirectional"))
    )
    (net (code "165") (name "unconnected-(4PIN_2-PadP$4)") (class "Default")
      (node (ref "4PIN_2") (pin "P$4") (pinfunction "P$4_P$4") (pintype "bidirectional"))
    )
    (net (code "166") (name "unconnected-(BATTERY-MUX-SC3-PadP$12)") (class "Default")
      (node (ref "BATTERY-MUX") (pin "P$12") (pinfunction "SC3_P$12") (pintype "bidirectional"))
    )
    (net (code "167") (name "unconnected-(BATTERY-MUX-SD3-PadP$11)") (class "Default")
      (node (ref "BATTERY-MUX") (pin "P$11") (pinfunction "SD3_P$11") (pintype "bidirectional"))
    )
    (net (code "168") (name "unconnected-(DVL_HOST_FTDI-CBUS2-Pad10)") (class "Default")
      (node (ref "DVL_HOST_FTDI") (pin "10") (pinfunction "CBUS2_10") (pintype "bidirectional"))
    )
    (net (code "169") (name "unconnected-(DVL_HOST_FTDI-CBUS3-Pad11)") (class "Default")
      (node (ref "DVL_HOST_FTDI") (pin "11") (pinfunction "CBUS3_11") (pintype "bidirectional"))
    )
    (net (code "170") (name "unconnected-(DVL_HOST_FTDI-CBUS4-Pad9)") (class "Default")
      (node (ref "DVL_HOST_FTDI") (pin "9") (pinfunction "CBUS4_9") (pintype "bidirectional"))
    )
    (net (code "171") (name "unconnected-(DVL_HOST_FTDI-OSCI-Pad27)") (class "Default")
      (node (ref "DVL_HOST_FTDI") (pin "27") (pinfunction "OSCI_27") (pintype "input"))
    )
    (net (code "172") (name "unconnected-(DVL_HOST_FTDI-OSCO-Pad28)") (class "Default")
      (node (ref "DVL_HOST_FTDI") (pin "28") (pinfunction "OSCO_28") (pintype "output"))
    )
    (net (code "173") (name "unconnected-(DVL_HOST_FTDI-~{DCD}-Pad7)") (class "Default")
      (node (ref "DVL_HOST_FTDI") (pin "7") (pinfunction "~{DCD}_7") (pintype "input"))
    )
    (net (code "174") (name "unconnected-(DVL_HOST_FTDI-~{DSR}-Pad6)") (class "Default")
      (node (ref "DVL_HOST_FTDI") (pin "6") (pinfunction "~{DSR}_6") (pintype "input"))
    )
    (net (code "175") (name "unconnected-(DVL_HOST_FTDI-~{DTR}-Pad31)") (class "Default")
      (node (ref "DVL_HOST_FTDI") (pin "31") (pinfunction "~{DTR}_31") (pintype "output"))
    )
    (net (code "176") (name "unconnected-(DVL_HOST_FTDI-~{RI}-Pad3)") (class "Default")
      (node (ref "DVL_HOST_FTDI") (pin "3") (pinfunction "~{RI}_3") (pintype "input"))
    )
    (net (code "177") (name "unconnected-(DVL_SLAVE_FTDI-CBUS2-Pad10)") (class "Default")
      (node (ref "DVL_SLAVE_FTDI") (pin "10") (pinfunction "CBUS2_10") (pintype "bidirectional"))
    )
    (net (code "178") (name "unconnected-(DVL_SLAVE_FTDI-CBUS3-Pad11)") (class "Default")
      (node (ref "DVL_SLAVE_FTDI") (pin "11") (pinfunction "CBUS3_11") (pintype "bidirectional"))
    )
    (net (code "179") (name "unconnected-(DVL_SLAVE_FTDI-CBUS4-Pad9)") (class "Default")
      (node (ref "DVL_SLAVE_FTDI") (pin "9") (pinfunction "CBUS4_9") (pintype "bidirectional"))
    )
    (net (code "180") (name "unconnected-(DVL_SLAVE_FTDI-OSCI-Pad27)") (class "Default")
      (node (ref "DVL_SLAVE_FTDI") (pin "27") (pinfunction "OSCI_27") (pintype "input"))
    )
    (net (code "181") (name "unconnected-(DVL_SLAVE_FTDI-OSCO-Pad28)") (class "Default")
      (node (ref "DVL_SLAVE_FTDI") (pin "28") (pinfunction "OSCO_28") (pintype "output"))
    )
    (net (code "182") (name "unconnected-(DVL_SLAVE_FTDI-~{DCD}-Pad7)") (class "Default")
      (node (ref "DVL_SLAVE_FTDI") (pin "7") (pinfunction "~{DCD}_7") (pintype "input"))
    )
    (net (code "183") (name "unconnected-(DVL_SLAVE_FTDI-~{DSR}-Pad6)") (class "Default")
      (node (ref "DVL_SLAVE_FTDI") (pin "6") (pinfunction "~{DSR}_6") (pintype "input"))
    )
    (net (code "184") (name "unconnected-(DVL_SLAVE_FTDI-~{DTR}-Pad31)") (class "Default")
      (node (ref "DVL_SLAVE_FTDI") (pin "31") (pinfunction "~{DTR}_31") (pintype "output"))
    )
    (net (code "185") (name "unconnected-(DVL_SLAVE_FTDI-~{RI}-Pad3)") (class "Default")
      (node (ref "DVL_SLAVE_FTDI") (pin "3") (pinfunction "~{RI}_3") (pintype "input"))
    )
    (net (code "186") (name "unconnected-(DVL_TTL-TO-RS232-RIN5-Pad18)") (class "Default")
      (node (ref "DVL_TTL-TO-RS232") (pin "18") (pinfunction "RIN5_18") (pintype "bidirectional"))
    )
    (net (code "187") (name "unconnected-(DVL_TTL-TO-RS232-ROUT5-Pad19)") (class "Default")
      (node (ref "DVL_TTL-TO-RS232") (pin "19") (pinfunction "ROUT5_19") (pintype "bidirectional"))
    )
    (net (code "188") (name "unconnected-(DVL_USB_HUB-NC-PadP$5)") (class "Default")
      (node (ref "DVL_USB_HUB") (pin "P$5") (pinfunction "NC_P$5") (pintype "bidirectional"))
    )
    (net (code "189") (name "unconnected-(DVL_USB_HUB-NC-PadP$6)") (class "Default")
      (node (ref "DVL_USB_HUB") (pin "P$6") (pinfunction "NC_P$6") (pintype "bidirectional"))
    )
    (net (code "190") (name "unconnected-(DVL_USB_HUB-OCS_N1-PadP$8)") (class "Default")
      (node (ref "DVL_USB_HUB") (pin "P$8") (pinfunction "OCS_N1_P$8") (pintype "bidirectional"))
    )
    (net (code "191") (name "unconnected-(DVL_USB_HUB-OCS_N2-PadP$12)") (class "Default")
      (node (ref "DVL_USB_HUB") (pin "P$12") (pinfunction "OCS_N2_P$12") (pintype "bidirectional"))
    )
    (net (code "192") (name "unconnected-(DVL_USB_HUB-XTALIN{slash}CLO\\KIN-PadP$24)") (class "Default")
      (node (ref "DVL_USB_HUB") (pin "P$24") (pinfunction "XTALIN/CLO\\KIN_P$24") (pintype "bidirectional"))
    )
    (net (code "193") (name "unconnected-(DVL_USB_HUB-XTALOUT-PadP$23)") (class "Default")
      (node (ref "DVL_USB_HUB") (pin "P$23") (pinfunction "XTALOUT_P$23") (pintype "bidirectional"))
    )
    (net (code "194") (name "unconnected-(IMU_FTDI-CBUS2-Pad10)") (class "Default")
      (node (ref "IMU_FTDI") (pin "10") (pinfunction "CBUS2_10") (pintype "bidirectional"))
    )
    (net (code "195") (name "unconnected-(IMU_FTDI-CBUS3-Pad11)") (class "Default")
      (node (ref "IMU_FTDI") (pin "11") (pinfunction "CBUS3_11") (pintype "bidirectional"))
    )
    (net (code "196") (name "unconnected-(IMU_FTDI-CBUS4-Pad9)") (class "Default")
      (node (ref "IMU_FTDI") (pin "9") (pinfunction "CBUS4_9") (pintype "bidirectional"))
    )
    (net (code "197") (name "unconnected-(IMU_FTDI-OSCI-Pad27)") (class "Default")
      (node (ref "IMU_FTDI") (pin "27") (pinfunction "OSCI_27") (pintype "input"))
    )
    (net (code "198") (name "unconnected-(IMU_FTDI-OSCO-Pad28)") (class "Default")
      (node (ref "IMU_FTDI") (pin "28") (pinfunction "OSCO_28") (pintype "output"))
    )
    (net (code "199") (name "unconnected-(IMU_FTDI-TXD-Pad30)") (class "Default")
      (node (ref "IMU_FTDI") (pin "30") (pinfunction "TXD_30") (pintype "output"))
    )
    (net (code "200") (name "unconnected-(IMU_FTDI-~{CTS}-Pad8)") (class "Default")
      (node (ref "IMU_FTDI") (pin "8") (pinfunction "~{CTS}_8") (pintype "input"))
    )
    (net (code "201") (name "unconnected-(IMU_FTDI-~{DCD}-Pad7)") (class "Default")
      (node (ref "IMU_FTDI") (pin "7") (pinfunction "~{DCD}_7") (pintype "input"))
    )
    (net (code "202") (name "unconnected-(IMU_FTDI-~{DSR}-Pad6)") (class "Default")
      (node (ref "IMU_FTDI") (pin "6") (pinfunction "~{DSR}_6") (pintype "input"))
    )
    (net (code "203") (name "unconnected-(IMU_FTDI-~{DTR}-Pad31)") (class "Default")
      (node (ref "IMU_FTDI") (pin "31") (pinfunction "~{DTR}_31") (pintype "output"))
    )
    (net (code "204") (name "unconnected-(IMU_FTDI-~{RI}-Pad3)") (class "Default")
      (node (ref "IMU_FTDI") (pin "3") (pinfunction "~{RI}_3") (pintype "input"))
    )
    (net (code "205") (name "unconnected-(IMU_FTDI-~{RTS}-Pad32)") (class "Default")
      (node (ref "IMU_FTDI") (pin "32") (pinfunction "~{RTS}_32") (pintype "output"))
    )
    (net (code "206") (name "unconnected-(IMU_TTL-TO-RS422-NC-PadP$12)") (class "Default")
      (node (ref "IMU_TTL-TO-RS422") (pin "P$12") (pinfunction "NC_P$12") (pintype "bidirectional"))
    )
    (net (code "207") (name "unconnected-(IMU_TTL-TO-RS422-NC-PadP$13)") (class "Default")
      (node (ref "IMU_TTL-TO-RS422") (pin "P$13") (pinfunction "NC_P$13") (pintype "bidirectional"))
    )
    (net (code "208") (name "unconnected-(IMU_TTL-TO-RS422-R2-IN-PadP$4)") (class "Default")
      (node (ref "IMU_TTL-TO-RS422") (pin "P$4") (pinfunction "R2-IN_P$4") (pintype "bidirectional"))
    )
    (net (code "209") (name "unconnected-(IMU_TTL-TO-RS422-R2-OUT-PadP$21)") (class "Default")
      (node (ref "IMU_TTL-TO-RS422") (pin "P$21") (pinfunction "R2-OUT_P$21") (pintype "bidirectional"))
    )
    (net (code "210") (name "unconnected-(IMU_TTL-TO-RS422-T1-IN-PadP$20)") (class "Default")
      (node (ref "IMU_TTL-TO-RS422") (pin "P$20") (pinfunction "T1-IN_P$20") (pintype "bidirectional"))
    )
    (net (code "211") (name "unconnected-(IMU_TTL-TO-RS422-T1-OUT-PadP$5)") (class "Default")
      (node (ref "IMU_TTL-TO-RS422") (pin "P$5") (pinfunction "T1-OUT_P$5") (pintype "bidirectional"))
    )
    (net (code "212") (name "unconnected-(IMU_TTL-TO-RS422-T2-IN-PadP$19)") (class "Default")
      (node (ref "IMU_TTL-TO-RS422") (pin "P$19") (pinfunction "T2-IN_P$19") (pintype "bidirectional"))
    )
    (net (code "213") (name "unconnected-(IMU_TTL-TO-RS422-T2-OUT-PadP$6)") (class "Default")
      (node (ref "IMU_TTL-TO-RS422") (pin "P$6") (pinfunction "T2-OUT_P$6") (pintype "bidirectional"))
    )
    (net (code "214") (name "unconnected-(IMU_TTL-TO-RS422-T3-IN-PadP$16)") (class "Default")
      (node (ref "IMU_TTL-TO-RS422") (pin "P$16") (pinfunction "T3-IN_P$16") (pintype "bidirectional"))
    )
    (net (code "215") (name "unconnected-(IMU_TTL-TO-RS422-T3-OUT(A)-PadP$11)") (class "Default")
      (node (ref "IMU_TTL-TO-RS422") (pin "P$11") (pinfunction "T3-OUT(A)_P$11") (pintype "bidirectional"))
    )
    (net (code "216") (name "unconnected-(IMU_TTL-TO-RS422-T3-OUT(B)-PadP$10)") (class "Default")
      (node (ref "IMU_TTL-TO-RS422") (pin "P$10") (pinfunction "T3-OUT(B)_P$10") (pintype "bidirectional"))
    )
    (net (code "217") (name "unconnected-(U$1-CFG_SEL2-PadP$14)") (class "Default")
      (node (ref "U$1") (pin "P$14") (pinfunction "CFG_SEL2_P$14") (pintype "bidirectional"))
    )
    (net (code "218") (name "unconnected-(U$1-GND-PadP$1)") (class "Default")
      (node (ref "U$1") (pin "P$1") (pinfunction "GND_P$1") (pintype "bidirectional"))
    )
    (net (code "219") (name "unconnected-(U$1-HS_IND{slash}CFG_SEL1-PadP$43)") (class "Default")
      (node (ref "U$1") (pin "P$43") (pinfunction "HS_IND/CFG_SEL1_P$43") (pintype "bidirectional"))
    )
    (net (code "220") (name "unconnected-(U$1-LED_A1_N{slash}PRT_SWP1-PadP$52)") (class "Default")
      (node (ref "U$1") (pin "P$52") (pinfunction "LED_A1_N/PRT_SWP1_P$52") (pintype "bidirectional"))
    )
    (net (code "221") (name "unconnected-(U$1-LED_A2_N{slash}PRT_SWP2-PadP$50)") (class "Default")
      (node (ref "U$1") (pin "P$50") (pinfunction "LED_A2_N/PRT_SWP2_P$50") (pintype "bidirectional"))
    )
    (net (code "222") (name "unconnected-(U$1-LED_A3_N{slash}PRT_SWP3-PadP$48)") (class "Default")
      (node (ref "U$1") (pin "P$48") (pinfunction "LED_A3_N/PRT_SWP3_P$48") (pintype "bidirectional"))
    )
    (net (code "223") (name "unconnected-(U$1-LED_A4_N{slash}PRT_SWP4-PadP$34)") (class "Default")
      (node (ref "U$1") (pin "P$34") (pinfunction "LED_A4_N/PRT_SWP4_P$34") (pintype "bidirectional"))
    )
    (net (code "224") (name "unconnected-(U$1-LED_A5_N{slash}PRT_SWP5-PadP$32)") (class "Default")
      (node (ref "U$1") (pin "P$32") (pinfunction "LED_A5_N/PRT_SWP5_P$32") (pintype "bidirectional"))
    )
    (net (code "225") (name "unconnected-(U$1-LED_A6_N{slash}PRT_SWP6-PadP$18)") (class "Default")
      (node (ref "U$1") (pin "P$18") (pinfunction "LED_A6_N/PRT_SWP6_P$18") (pintype "bidirectional"))
    )
    (net (code "226") (name "unconnected-(U$1-LED_A7_N{slash}PRT_SWP7-PadP$16)") (class "Default")
      (node (ref "U$1") (pin "P$16") (pinfunction "LED_A7_N/PRT_SWP7_P$16") (pintype "bidirectional"))
    )
    (net (code "227") (name "unconnected-(U$1-LED_B1_N{slash}BOOST0-PadP$51)") (class "Default")
      (node (ref "U$1") (pin "P$51") (pinfunction "LED_B1_N/BOOST0_P$51") (pintype "bidirectional"))
    )
    (net (code "228") (name "unconnected-(U$1-LED_B2_N{slash}BOOST1-PadP$49)") (class "Default")
      (node (ref "U$1") (pin "P$49") (pinfunction "LED_B2_N/BOOST1_P$49") (pintype "bidirectional"))
    )
    (net (code "229") (name "unconnected-(U$1-LED_B3_N{slash}GANG_EN-PadP$35)") (class "Default")
      (node (ref "U$1") (pin "P$35") (pinfunction "LED_B3_N/GANG_EN_P$35") (pintype "bidirectional"))
    )
    (net (code "230") (name "unconnected-(U$1-LED_B4_N-PadP$33)") (class "Default")
      (node (ref "U$1") (pin "P$33") (pinfunction "LED_B4_N_P$33") (pintype "bidirectional"))
    )
    (net (code "231") (name "unconnected-(U$1-LED_B5_N-PadP$19)") (class "Default")
      (node (ref "U$1") (pin "P$19") (pinfunction "LED_B5_N_P$19") (pintype "bidirectional"))
    )
    (net (code "232") (name "unconnected-(U$1-LED_B6_N-PadP$17)") (class "Default")
      (node (ref "U$1") (pin "P$17") (pinfunction "LED_B6_N_P$17") (pintype "bidirectional"))
    )
    (net (code "233") (name "unconnected-(U$1-LED_B7_N-PadP$15)") (class "Default")
      (node (ref "U$1") (pin "P$15") (pinfunction "LED_B7_N_P$15") (pintype "bidirectional"))
    )
    (net (code "234") (name "unconnected-(U$1-OCS1_N-PadP$29)") (class "Default")
      (node (ref "U$1") (pin "P$29") (pinfunction "OCS1_N_P$29") (pintype "bidirectional"))
    )
    (net (code "235") (name "unconnected-(U$1-OCS2_N-PadP$28)") (class "Default")
      (node (ref "U$1") (pin "P$28") (pinfunction "OCS2_N_P$28") (pintype "bidirectional"))
    )
    (net (code "236") (name "unconnected-(U$1-OCS3_N-PadP$23)") (class "Default")
      (node (ref "U$1") (pin "P$23") (pinfunction "OCS3_N_P$23") (pintype "bidirectional"))
    )
    (net (code "237") (name "unconnected-(U$1-OCS4_N-PadP$22)") (class "Default")
      (node (ref "U$1") (pin "P$22") (pinfunction "OCS4_N_P$22") (pintype "bidirectional"))
    )
    (net (code "238") (name "unconnected-(U$1-OCS5_N-PadP$36)") (class "Default")
      (node (ref "U$1") (pin "P$36") (pinfunction "OCS5_N_P$36") (pintype "bidirectional"))
    )
    (net (code "239") (name "unconnected-(U$1-OCS6_N-PadP$39)") (class "Default")
      (node (ref "U$1") (pin "P$39") (pinfunction "OCS6_N_P$39") (pintype "bidirectional"))
    )
    (net (code "240") (name "unconnected-(U$1-OCS7_N-PadP$38)") (class "Default")
      (node (ref "U$1") (pin "P$38") (pinfunction "OCS7_N_P$38") (pintype "bidirectional"))
    )
    (net (code "241") (name "unconnected-(U$1-PRTPWR1-PadP$30)") (class "Default")
      (node (ref "U$1") (pin "P$30") (pinfunction "PRTPWR1_P$30") (pintype "bidirectional"))
    )
    (net (code "242") (name "unconnected-(U$1-PRTPWR2-PadP$27)") (class "Default")
      (node (ref "U$1") (pin "P$27") (pinfunction "PRTPWR2_P$27") (pintype "bidirectional"))
    )
    (net (code "243") (name "unconnected-(U$1-PRTPWR3-PadP$24)") (class "Default")
      (node (ref "U$1") (pin "P$24") (pinfunction "PRTPWR3_P$24") (pintype "bidirectional"))
    )
    (net (code "244") (name "unconnected-(U$1-PRTPWR4-PadP$21)") (class "Default")
      (node (ref "U$1") (pin "P$21") (pinfunction "PRTPWR4_P$21") (pintype "bidirectional"))
    )
    (net (code "245") (name "unconnected-(U$1-PRTPWR5-PadP$31)") (class "Default")
      (node (ref "U$1") (pin "P$31") (pinfunction "PRTPWR5_P$31") (pintype "bidirectional"))
    )
    (net (code "246") (name "unconnected-(U$1-PRTPWR6-PadP$40)") (class "Default")
      (node (ref "U$1") (pin "P$40") (pinfunction "PRTPWR6_P$40") (pintype "bidirectional"))
    )
    (net (code "247") (name "unconnected-(U$1-PRTPWR7-PadP$37)") (class "Default")
      (node (ref "U$1") (pin "P$37") (pinfunction "PRTPWR7_P$37") (pintype "bidirectional"))
    )
    (net (code "248") (name "unconnected-(U$1-RBIAS-PadP$64)") (class "Default")
      (node (ref "U$1") (pin "P$64") (pinfunction "RBIAS_P$64") (pintype "bidirectional"))
    )
    (net (code "249") (name "unconnected-(U$1-RESET_N-PadP$44)") (class "Default")
      (node (ref "U$1") (pin "P$44") (pinfunction "RESET_N_P$44") (pintype "bidirectional"))
    )
    (net (code "250") (name "unconnected-(U$1-SCL{slash}SMBCLK{slash}CFG_SEL0-PadP$42)") (class "Default")
      (node (ref "U$1") (pin "P$42") (pinfunction "SCL/SMBCLK/CFG_SEL0_P$42") (pintype "bidirectional"))
    )
    (net (code "251") (name "unconnected-(U$1-SDA{slash}SMBDATA{slash}NON_REM1-PadP$41)") (class "Default")
      (node (ref "U$1") (pin "P$41") (pinfunction "SDA/SMBDATA/NON_REM1_P$41") (pintype "bidirectional"))
    )
    (net (code "252") (name "unconnected-(U$1-SUSP_IND{slash}LOCAL_PWR{slash}NON_REM0-PadP$46)") (class "Default")
      (node (ref "U$1") (pin "P$46") (pinfunction "SUSP_IND/LOCAL_PWR/NON_REM0_P$46") (pintype "bidirectional"))
    )
    (net (code "253") (name "unconnected-(U$1-TEST-PadP$20)") (class "Default")
      (node (ref "U$1") (pin "P$20") (pinfunction "TEST_P$20") (pintype "bidirectional"))
    )
    (net (code "254") (name "unconnected-(U$1-USBDN1_DM{slash}PRT_DIS_M1-PadP$2)") (class "Default")
      (node (ref "U$1") (pin "P$2") (pinfunction "USBDN1_DM/PRT_DIS_M1_P$2") (pintype "bidirectional"))
    )
    (net (code "255") (name "unconnected-(U$1-USBDN1_DP{slash}PRT_DIS_P1-PadP$3)") (class "Default")
      (node (ref "U$1") (pin "P$3") (pinfunction "USBDN1_DP/PRT_DIS_P1_P$3") (pintype "bidirectional"))
    )
    (net (code "256") (name "unconnected-(U$1-USBDN2_DM{slash}PRT_DIS_M2-PadP$4)") (class "Default")
      (node (ref "U$1") (pin "P$4") (pinfunction "USBDN2_DM/PRT_DIS_M2_P$4") (pintype "bidirectional"))
    )
    (net (code "257") (name "unconnected-(U$1-USBDN2_DP{slash}PRT_DIS_P2-PadP$5)") (class "Default")
      (node (ref "U$1") (pin "P$5") (pinfunction "USBDN2_DP/PRT_DIS_P2_P$5") (pintype "bidirectional"))
    )
    (net (code "258") (name "unconnected-(U$1-USBDN3_DM{slash}PRT_DIS_M3-PadP$7)") (class "Default")
      (node (ref "U$1") (pin "P$7") (pinfunction "USBDN3_DM/PRT_DIS_M3_P$7") (pintype "bidirectional"))
    )
    (net (code "259") (name "unconnected-(U$1-USBDN3_DP{slash}PRT_DIS_P3-PadP$8)") (class "Default")
      (node (ref "U$1") (pin "P$8") (pinfunction "USBDN3_DP/PRT_DIS_P3_P$8") (pintype "bidirectional"))
    )
    (net (code "260") (name "unconnected-(U$1-USBDN4_DM{slash}PRT_DIS_M4-PadP$9)") (class "Default")
      (node (ref "U$1") (pin "P$9") (pinfunction "USBDN4_DM/PRT_DIS_M4_P$9") (pintype "bidirectional"))
    )
    (net (code "261") (name "unconnected-(U$1-USBDN4_DP{slash}PRT_DIS_P4-PadP$10)") (class "Default")
      (node (ref "U$1") (pin "P$10") (pinfunction "USBDN4_DP/PRT_DIS_P4_P$10") (pintype "bidirectional"))
    )
    (net (code "262") (name "unconnected-(U$1-USBDN5_DM{slash}PRT_DIS_M5-PadP$12)") (class "Default")
      (node (ref "U$1") (pin "P$12") (pinfunction "USBDN5_DM/PRT_DIS_M5_P$12") (pintype "bidirectional"))
    )
    (net (code "263") (name "unconnected-(U$1-USBDN5_DP{slash}PRT_DIS_P5-PadP$13)") (class "Default")
      (node (ref "U$1") (pin "P$13") (pinfunction "USBDN5_DP/PRT_DIS_P5_P$13") (pintype "bidirectional"))
    )
    (net (code "264") (name "unconnected-(U$1-USBDN6_DM{slash}PRT_DIS_M6-PadP$54)") (class "Default")
      (node (ref "U$1") (pin "P$54") (pinfunction "USBDN6_DM/PRT_DIS_M6_P$54") (pintype "bidirectional"))
    )
    (net (code "265") (name "unconnected-(U$1-USBDN6_DP{slash}PRT_DIS_P6-PadP$55)") (class "Default")
      (node (ref "U$1") (pin "P$55") (pinfunction "USBDN6_DP/PRT_DIS_P6_P$55") (pintype "bidirectional"))
    )
    (net (code "266") (name "unconnected-(U$1-USBDN7_DM{slash}PRT_DIS_M7-PadP$56)") (class "Default")
      (node (ref "U$1") (pin "P$56") (pinfunction "USBDN7_DM/PRT_DIS_M7_P$56") (pintype "bidirectional"))
    )
    (net (code "267") (name "unconnected-(U$1-USBDN7_DP{slash}PRT_DIS_P7-PadP$57)") (class "Default")
      (node (ref "U$1") (pin "P$57") (pinfunction "USBDN7_DP/PRT_DIS_P7_P$57") (pintype "bidirectional"))
    )
    (net (code "268") (name "unconnected-(U$1-USBUP_DM-PadP$59)") (class "Default")
      (node (ref "U$1") (pin "P$59") (pinfunction "USBUP_DM_P$59") (pintype "bidirectional"))
    )
    (net (code "269") (name "unconnected-(U$1-USBUP_DP-PadP$60)") (class "Default")
      (node (ref "U$1") (pin "P$60") (pinfunction "USBUP_DP_P$60") (pintype "bidirectional"))
    )
    (net (code "270") (name "unconnected-(U$1-VBUS_DET-PadP$45)") (class "Default")
      (node (ref "U$1") (pin "P$45") (pinfunction "VBUS_DET_P$45") (pintype "bidirectional"))
    )
    (net (code "271") (name "unconnected-(U$1-VDD18-PadP$26)") (class "Default")
      (node (ref "U$1") (pin "P$26") (pinfunction "VDD18_P$26") (pintype "bidirectional"))
    )
    (net (code "272") (name "unconnected-(U$1-VDD18PLL-PadP$63)") (class "Default")
      (node (ref "U$1") (pin "P$63") (pinfunction "VDD18PLL_P$63") (pintype "bidirectional"))
    )
    (net (code "273") (name "unconnected-(U$1-VDD33-PadP$47)") (class "Default")
      (node (ref "U$1") (pin "P$47") (pinfunction "VDD33_P$47") (pintype "bidirectional"))
    )
    (net (code "274") (name "unconnected-(U$1-VDD33CR-PadP$25)") (class "Default")
      (node (ref "U$1") (pin "P$25") (pinfunction "VDD33CR_P$25") (pintype "bidirectional"))
    )
    (net (code "275") (name "unconnected-(U$1-VDD33PLL-PadP$65)") (class "Default")
      (node (ref "U$1") (pin "P$65") (pinfunction "VDD33PLL_P$65") (pintype "bidirectional"))
    )
    (net (code "276") (name "unconnected-(U$1-VDDA33-PadP$6)") (class "Default")
      (node (ref "U$1") (pin "P$6") (pinfunction "VDDA33_P$6") (pintype "bidirectional"))
    )
    (net (code "277") (name "unconnected-(U$1-VDDA33-PadP$11)") (class "Default")
      (node (ref "U$1") (pin "P$11") (pinfunction "VDDA33_P$11") (pintype "bidirectional"))
    )
    (net (code "278") (name "unconnected-(U$1-VDDA33-PadP$53)") (class "Default")
      (node (ref "U$1") (pin "P$53") (pinfunction "VDDA33_P$53") (pintype "bidirectional"))
    )
    (net (code "279") (name "unconnected-(U$1-VDDA33-PadP$58)") (class "Default")
      (node (ref "U$1") (pin "P$58") (pinfunction "VDDA33_P$58") (pintype "bidirectional"))
    )
    (net (code "280") (name "unconnected-(U$1-XTAL1{slash}CLKIN-PadP$62)") (class "Default")
      (node (ref "U$1") (pin "P$62") (pinfunction "XTAL1/CLKIN_P$62") (pintype "bidirectional"))
    )
    (net (code "281") (name "unconnected-(U$1-XTAL2-PadP$61)") (class "Default")
      (node (ref "U$1") (pin "P$61") (pinfunction "XTAL2_P$61") (pintype "bidirectional"))
    )
    (net (code "282") (name "unconnected-(U$2-I{slash}O_1-PadP$2)") (class "Default")
      (node (ref "U$2") (pin "P$2") (pinfunction "I/O_1_P$2") (pintype "bidirectional"))
    )
    (net (code "283") (name "unconnected-(U$2-I{slash}O_2-PadP$3)") (class "Default")
      (node (ref "U$2") (pin "P$3") (pinfunction "I/O_2_P$3") (pintype "bidirectional"))
    )
    (net (code "284") (name "unconnected-(U$3-I{slash}O_1-PadP$2)") (class "Default")
      (node (ref "U$3") (pin "P$2") (pinfunction "I/O_1_P$2") (pintype "bidirectional"))
    )
    (net (code "285") (name "unconnected-(U$3-I{slash}O_2-PadP$3)") (class "Default")
      (node (ref "U$3") (pin "P$3") (pinfunction "I/O_2_P$3") (pintype "bidirectional"))
    )
    (net (code "286") (name "unconnected-(U$4-I{slash}O_1-PadP$2)") (class "Default")
      (node (ref "U$4") (pin "P$2") (pinfunction "I/O_1_P$2") (pintype "bidirectional"))
    )
    (net (code "287") (name "unconnected-(U$4-I{slash}O_2-PadP$3)") (class "Default")
      (node (ref "U$4") (pin "P$3") (pinfunction "I/O_2_P$3") (pintype "bidirectional"))
    )
    (net (code "288") (name "unconnected-(U$5-I{slash}O_1-PadP$2)") (class "Default")
      (node (ref "U$5") (pin "P$2") (pinfunction "I/O_1_P$2") (pintype "bidirectional"))
    )
    (net (code "289") (name "unconnected-(U$5-I{slash}O_2-PadP$3)") (class "Default")
      (node (ref "U$5") (pin "P$3") (pinfunction "I/O_2_P$3") (pintype "bidirectional"))
    )
    (net (code "290") (name "unconnected-(U$6-I{slash}O_1-PadP$2)") (class "Default")
      (node (ref "U$6") (pin "P$2") (pinfunction "I/O_1_P$2") (pintype "bidirectional"))
    )
    (net (code "291") (name "unconnected-(U$6-I{slash}O_2-PadP$3)") (class "Default")
      (node (ref "U$6") (pin "P$3") (pinfunction "I/O_2_P$3") (pintype "bidirectional"))
    )
    (net (code "292") (name "unconnected-(U$7-I{slash}O_1-PadP$2)") (class "Default")
      (node (ref "U$7") (pin "P$2") (pinfunction "I/O_1_P$2") (pintype "bidirectional"))
    )
    (net (code "293") (name "unconnected-(U$7-I{slash}O_2-PadP$3)") (class "Default")
      (node (ref "U$7") (pin "P$3") (pinfunction "I/O_2_P$3") (pintype "bidirectional"))
    )
    (net (code "294") (name "unconnected-(U$8-I{slash}O_1-PadP$2)") (class "Default")
      (node (ref "U$8") (pin "P$2") (pinfunction "I/O_1_P$2") (pintype "bidirectional"))
    )
    (net (code "295") (name "unconnected-(U$8-I{slash}O_2-PadP$3)") (class "Default")
      (node (ref "U$8") (pin "P$3") (pinfunction "I/O_2_P$3") (pintype "bidirectional"))
    )
    (net (code "296") (name "unconnected-(U$9-I{slash}O_1-PadP$2)") (class "Default")
      (node (ref "U$9") (pin "P$2") (pinfunction "I/O_1_P$2") (pintype "bidirectional"))
    )
    (net (code "297") (name "unconnected-(U$9-I{slash}O_2-PadP$3)") (class "Default")
      (node (ref "U$9") (pin "P$3") (pinfunction "I/O_2_P$3") (pintype "bidirectional"))
    )
    (net (code "298") (name "unconnected-(U$10-I{slash}O_1-PadP$2)") (class "Default")
      (node (ref "U$10") (pin "P$2") (pinfunction "I/O_1_P$2") (pintype "bidirectional"))
    )
    (net (code "299") (name "unconnected-(U$10-I{slash}O_2-PadP$3)") (class "Default")
      (node (ref "U$10") (pin "P$3") (pinfunction "I/O_2_P$3") (pintype "bidirectional"))
    )
    (net (code "300") (name "unconnected-(U$11-I{slash}O_1-PadP$2)") (class "Default")
      (node (ref "U$11") (pin "P$2") (pinfunction "I/O_1_P$2") (pintype "bidirectional"))
    )
    (net (code "301") (name "unconnected-(U$11-I{slash}O_2-PadP$3)") (class "Default")
      (node (ref "U$11") (pin "P$3") (pinfunction "I/O_2_P$3") (pintype "bidirectional"))
    )
    (net (code "302") (name "unconnected-(U$12-I{slash}O_1-PadP$2)") (class "Default")
      (node (ref "U$12") (pin "P$2") (pinfunction "I/O_1_P$2") (pintype "bidirectional"))
    )
    (net (code "303") (name "unconnected-(U$12-I{slash}O_2-PadP$3)") (class "Default")
      (node (ref "U$12") (pin "P$3") (pinfunction "I/O_2_P$3") (pintype "bidirectional"))
    )
    (net (code "304") (name "unconnected-(U$13-I{slash}O_1-PadP$2)") (class "Default")
      (node (ref "U$13") (pin "P$2") (pinfunction "I/O_1_P$2") (pintype "bidirectional"))
    )
    (net (code "305") (name "unconnected-(U$13-I{slash}O_2-PadP$3)") (class "Default")
      (node (ref "U$13") (pin "P$3") (pinfunction "I/O_2_P$3") (pintype "bidirectional"))
    )
    (net (code "306") (name "unconnected-(U$14-I{slash}O_1-PadP$2)") (class "Default")
      (node (ref "U$14") (pin "P$2") (pinfunction "I/O_1_P$2") (pintype "bidirectional"))
    )
    (net (code "307") (name "unconnected-(U$14-I{slash}O_2-PadP$3)") (class "Default")
      (node (ref "U$14") (pin "P$3") (pinfunction "I/O_2_P$3") (pintype "bidirectional"))
    )
    (net (code "308") (name "unconnected-(U$15-PadP$1)") (class "Default")
      (node (ref "U$15") (pin "P$1") (pinfunction "P$1_P$1") (pintype "bidirectional"))
    )
    (net (code "309") (name "unconnected-(U$15-PadP$2)") (class "Default")
      (node (ref "U$15") (pin "P$2") (pinfunction "P$2_P$2") (pintype "bidirectional"))
    )
    (net (code "310") (name "unconnected-(U$15-PadP$3)") (class "Default")
      (node (ref "U$15") (pin "P$3") (pinfunction "P$3_P$3") (pintype "bidirectional"))
    )
    (net (code "311") (name "unconnected-(U$15-PadP$4)") (class "Default")
      (node (ref "U$15") (pin "P$4") (pinfunction "P$4_P$4") (pintype "bidirectional"))
    )
    (net (code "312") (name "unconnected-(U$15-PadP$5)") (class "Default")
      (node (ref "U$15") (pin "P$5") (pinfunction "P$5_P$5") (pintype "bidirectional"))
    )
    (net (code "313") (name "unconnected-(U$15-PadP$6)") (class "Default")
      (node (ref "U$15") (pin "P$6") (pinfunction "P$6_P$6") (pintype "bidirectional"))
    )
    (net (code "314") (name "unconnected-(U$16-PadP$1)") (class "Default")
      (node (ref "U$16") (pin "P$1") (pinfunction "P$1_P$1") (pintype "bidirectional"))
    )
    (net (code "315") (name "unconnected-(U$16-PadP$2)") (class "Default")
      (node (ref "U$16") (pin "P$2") (pinfunction "P$2_P$2") (pintype "bidirectional"))
    )
    (net (code "316") (name "unconnected-(U$16-PadP$3)") (class "Default")
      (node (ref "U$16") (pin "P$3") (pinfunction "P$3_P$3") (pintype "bidirectional"))
    )
    (net (code "317") (name "unconnected-(U$16-PadP$4)") (class "Default")
      (node (ref "U$16") (pin "P$4") (pinfunction "P$4_P$4") (pintype "bidirectional"))
    )
    (net (code "318") (name "unconnected-(U$16-PadP$5)") (class "Default")
      (node (ref "U$16") (pin "P$5") (pinfunction "P$5_P$5") (pintype "bidirectional"))
    )
    (net (code "319") (name "unconnected-(U$16-PadP$6)") (class "Default")
      (node (ref "U$16") (pin "P$6") (pinfunction "P$6_P$6") (pintype "bidirectional"))
    )
  )
)
